# Project_Arduino_DUE_shield.net
KiCad netlist of a schematic drawn in Altium Designer
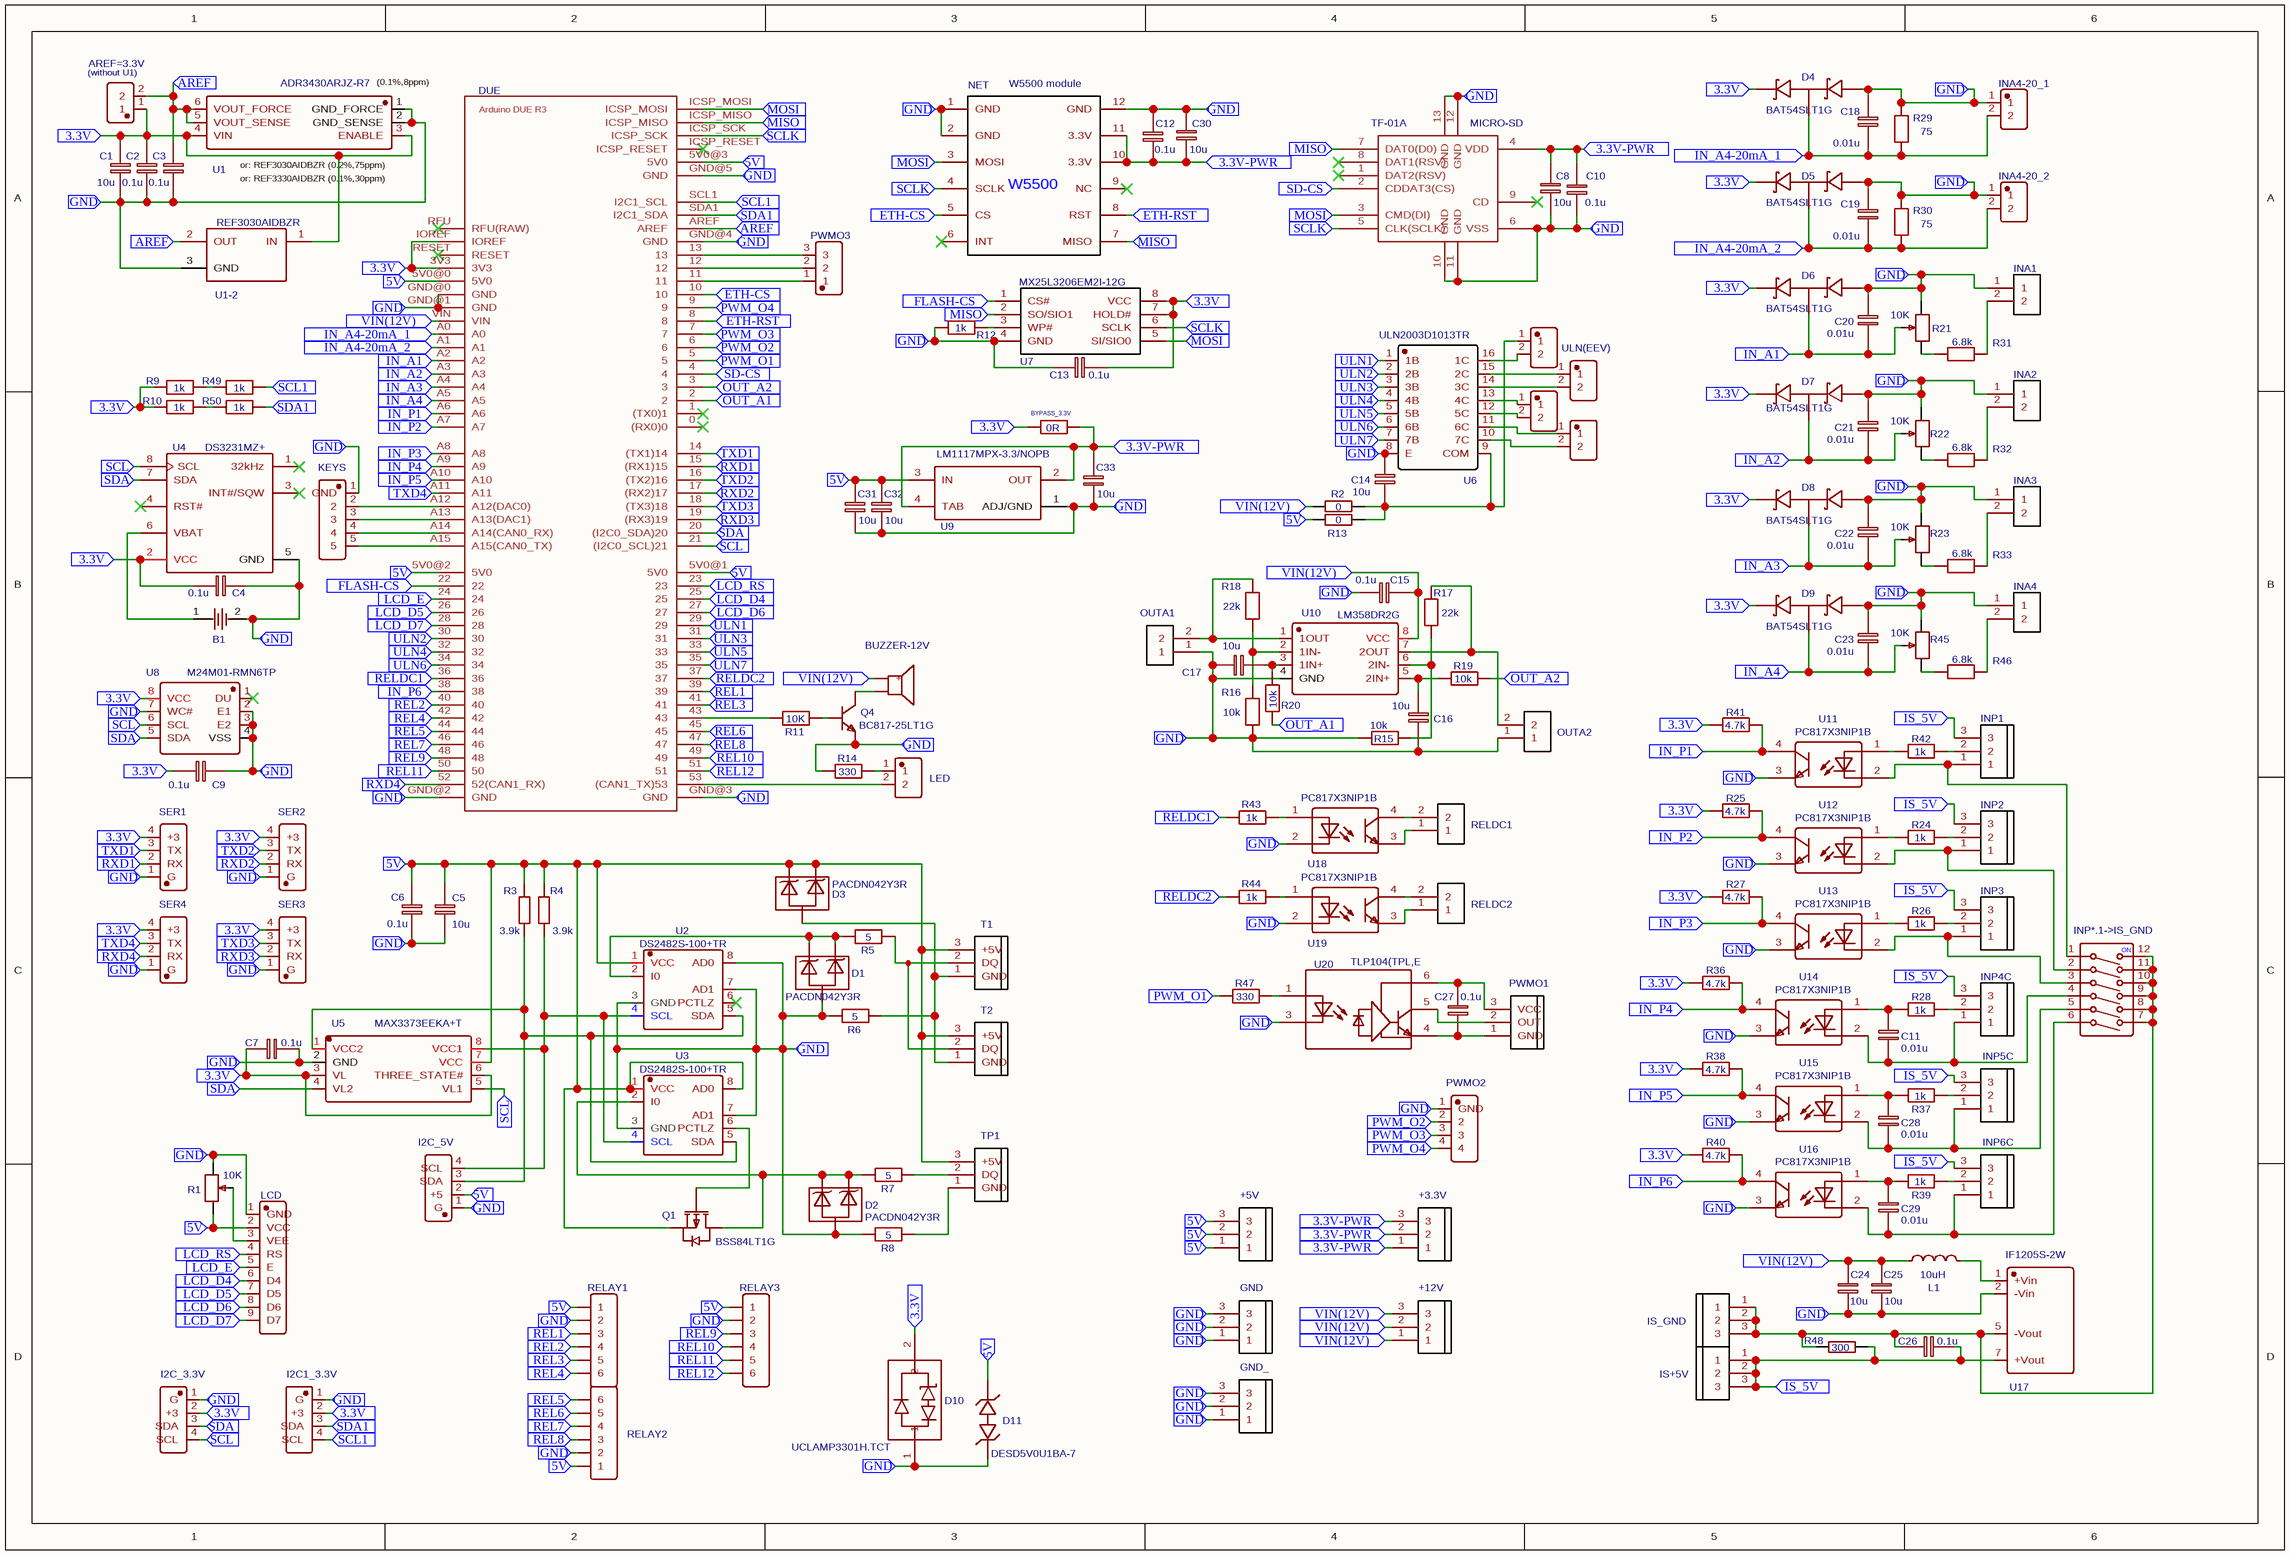
[diagram p0: Project_Arduino DUE shield.schdoc]

(export (version "E")
  (design (tool "Eeschema 10.0.6"))
  (components
    (comp (ref "+3.3V")
      (value "KF128L-5.08-3P")
      (fields (field (name "BOM_SUPPLIER PART") "C474941"))
      (libsource (lib "altium-import") (part "root_3_KF128L-5.08-3P_"))
    )
    (comp (ref "+5V")
      (value "KF128L-5.08-3P")
      (fields (field (name "BOM_SUPPLIER PART") "C474941"))
      (libsource (lib "altium-import") (part "root_3_KF128L-5.08-3P_"))
    )
    (comp (ref "+12V")
      (value "KF128L-5.08-3P")
      (fields (field (name "BOM_SUPPLIER PART") "C474941"))
      (libsource (lib "altium-import") (part "root_3_KF128L-5.08-3P_"))
    )
    (comp (ref "AREF=3.3V")
      (value "A2541WV-2P")
      (fields (field (name "BOM_SUPPLIER PART") "C225477") (field (name "CONTRIBUTOR") "LCSC"))
      (libsource (lib "altium-import") (part "root_2_A2541WV-2P_"))
    )
    (comp (ref "B1")
      (value "CR2032-BS-2-1")
      (fields (field (name "BOM_MANUFACTURER PART") "BS-2-1") (field (name "BOM_SUPPLIER PART") "C70376"))
      (libsource (lib "altium-import") (part "root_0_CR2032-BS-2-1_"))
    )
    (comp (ref "BUZZER-12V")
      (value "TMB12A12")
      (fields (field (name "BOM_SUPPLIER PART") "C96079"))
      (libsource (lib "altium-import") (part "root_0_TMB12A12_"))
    )
    (comp (ref "BYPASS_3.3V")
      (value "0R")
      (fields (field (name "CONTRIBUTOR") "LCEDA_Lib"))
      (libsource (lib "altium-import") (part "root_0_0R_"))
    )
    (comp (ref "C1")
      (value "10u")
      (fields
        (field (name "BOM_MANUFACTURER PART") "CL21A106KAYNNNE")
        (field (name "BOM_SUPPLIER PART") "C15850")
      )
      (libsource (lib "altium-import") (part "root_0_10u_"))
    )
    (comp (ref "C2")
      (value "0.1u")
      (fields
        (field (name "BOM_MANUFACTURER PART") "CC0603KRX7R9BB104")
        (field (name "BOM_SUPPLIER PART") "C14663")
      )
      (libsource (lib "") (part "root_0_0.1u__2"))
    )
    (comp (ref "C3")
      (value "0.1u")
      (fields
        (field (name "BOM_MANUFACTURER PART") "CC0603KRX7R9BB104")
        (field (name "BOM_SUPPLIER PART") "C14663")
      )
      (libsource (lib "") (part "root_0_0.1u__2"))
    )
    (comp (ref "C4")
      (value "0.1u")
      (fields
        (field (name "BOM_MANUFACTURER PART") "CC0603KRX7R9BB104")
        (field (name "BOM_SUPPLIER PART") "C14663")
      )
      (libsource (lib "") (part "root_3_0.1u__1"))
    )
    (comp (ref "C5")
      (value "10u")
      (fields
        (field (name "BOM_MANUFACTURER PART") "CL21A106KAYNNNE")
        (field (name "BOM_SUPPLIER PART") "C15850")
      )
      (libsource (lib "altium-import") (part "root_0_10u_"))
    )
    (comp (ref "C6")
      (value "0.1u")
      (fields
        (field (name "BOM_MANUFACTURER PART") "CC0603KRX7R9BB104")
        (field (name "BOM_SUPPLIER PART") "C14663")
      )
      (libsource (lib "") (part "root_0_0.1u__2"))
    )
    (comp (ref "C7")
      (value "0.1u")
      (fields
        (field (name "BOM_MANUFACTURER PART") "CC0603KRX7R9BB104")
        (field (name "BOM_SUPPLIER PART") "C14663")
      )
      (libsource (lib "") (part "root_1_0.1u__2"))
    )
    (comp (ref "C8")
      (value "10u")
      (fields
        (field (name "BOM_SUPPLIER PART") "C15850")
        (field (name "BOM_MANUFACTURER PART") "CL21A106KAYNNNE")
        (field (name "CONTRIBUTOR") "LCEDA_Lib")
      )
      (libsource (lib "altium-import") (part "root_3_10u_"))
    )
    (comp (ref "C9")
      (value "0.1u")
      (fields
        (field (name "BOM_MANUFACTURER PART") "CC0603KRX7R9BB104")
        (field (name "BOM_SUPPLIER PART") "C14663")
      )
      (libsource (lib "") (part "root_3_0.1u__1"))
    )
    (comp (ref "C10")
      (value "0.1u")
      (fields
        (field (name "BOM_SUPPLIER PART") "C14663")
        (field (name "BOM_MANUFACTURER PART") "CC0603KRX7R9BB104")
        (field (name "CONTRIBUTOR") "LCEDA_Lib")
      )
      (libsource (lib "") (part "root_1_0.1u__1"))
    )
    (comp (ref "C11")
      (value "0.01u")
      (fields
        (field (name "BOM_SUPPLIER PART") "C57112")
        (field (name "BOM_MANUFACTURER PART") "0603B103K500NT")
        (field (name "CONTRIBUTOR") "LCEDA_Lib")
      )
      (libsource (lib "altium-import") (part "root_3_0.01u_"))
    )
    (comp (ref "C12")
      (value "0.1u")
      (fields
        (field (name "BOM_SUPPLIER PART") "C14663")
        (field (name "BOM_MANUFACTURER PART") "CC0603KRX7R9BB104")
        (field (name "CONTRIBUTOR") "LCEDA_Lib")
      )
      (libsource (lib "") (part "root_1_0.1u__1"))
    )
    (comp (ref "C13")
      (value "0.1u")
      (fields
        (field (name "BOM_SUPPLIER PART") "C14663")
        (field (name "BOM_MANUFACTURER PART") "CC0603KRX7R9BB104")
        (field (name "CONTRIBUTOR") "LCEDA_Lib")
      )
      (libsource (lib "") (part "root_0_0.1u__1"))
    )
    (comp (ref "C14")
      (value "10u")
      (fields
        (field (name "BOM_MANUFACTURER PART") "CL21A106KAYNNNE")
        (field (name "BOM_SUPPLIER PART") "C15850")
      )
      (libsource (lib "") (part "root_0_10u__1"))
    )
    (comp (ref "C15")
      (value "0.1u")
      (fields
        (field (name "BOM_MANUFACTURER PART") "CC0603KRX7R9BB104")
        (field (name "BOM_SUPPLIER PART") "C14663")
      )
      (libsource (lib "altium-import") (part "root_3_0.1u_"))
    )
    (comp (ref "C16")
      (value "10u")
      (fields
        (field (name "BOM_MANUFACTURER PART") "CL21A106KAYNNNE")
        (field (name "BOM_SUPPLIER PART") "C15850")
      )
      (libsource (lib "altium-import") (part "root_0_10u_"))
    )
    (comp (ref "C17")
      (value "10u")
      (fields
        (field (name "BOM_MANUFACTURER PART") "CL21A106KAYNNNE")
        (field (name "BOM_SUPPLIER PART") "C15850")
      )
      (libsource (lib "altium-import") (part "root_1_10u_"))
    )
    (comp (ref "C18")
      (value "0.01u")
      (fields
        (field (name "BOM_MANUFACTURER PART") "0603B103K500NT")
        (field (name "BOM_SUPPLIER PART") "C57112")
      )
      (libsource (lib "altium-import") (part "root_0_0.01u_"))
    )
    (comp (ref "C19")
      (value "0.01u")
      (fields
        (field (name "BOM_MANUFACTURER PART") "0603B103K500NT")
        (field (name "BOM_SUPPLIER PART") "C57112")
      )
      (libsource (lib "altium-import") (part "root_0_0.01u_"))
    )
    (comp (ref "C20")
      (value "0.01u")
      (fields
        (field (name "BOM_MANUFACTURER PART") "0603B103K500NT")
        (field (name "BOM_SUPPLIER PART") "C57112")
      )
      (libsource (lib "altium-import") (part "root_0_0.01u_"))
    )
    (comp (ref "C21")
      (value "0.01u")
      (fields
        (field (name "BOM_MANUFACTURER PART") "0603B103K500NT")
        (field (name "BOM_SUPPLIER PART") "C57112")
      )
      (libsource (lib "altium-import") (part "root_0_0.01u_"))
    )
    (comp (ref "C22")
      (value "0.01u")
      (fields
        (field (name "BOM_MANUFACTURER PART") "0603B103K500NT")
        (field (name "BOM_SUPPLIER PART") "C57112")
      )
      (libsource (lib "altium-import") (part "root_0_0.01u_"))
    )
    (comp (ref "C23")
      (value "0.01u")
      (fields
        (field (name "BOM_MANUFACTURER PART") "0603B103K500NT")
        (field (name "BOM_SUPPLIER PART") "C57112")
      )
      (libsource (lib "altium-import") (part "root_0_0.01u_"))
    )
    (comp (ref "C24")
      (value "10u")
      (fields
        (field (name "BOM_SUPPLIER PART") "C15850")
        (field (name "BOM_MANUFACTURER PART") "CL21A106KAYNNNE")
        (field (name "CONTRIBUTOR") "LCEDA_Lib")
      )
      (libsource (lib "") (part "root_1_10u__1"))
    )
    (comp (ref "C25")
      (value "10u")
      (fields
        (field (name "BOM_SUPPLIER PART") "C15850")
        (field (name "BOM_MANUFACTURER PART") "CL21A106KAYNNNE")
        (field (name "CONTRIBUTOR") "LCEDA_Lib")
      )
      (libsource (lib "") (part "root_1_10u__1"))
    )
    (comp (ref "C26")
      (value "0.1u")
      (fields
        (field (name "BOM_MANUFACTURER PART") "CC0603KRX7R9BB104")
        (field (name "BOM_SUPPLIER PART") "C14663")
      )
      (libsource (lib "altium-import") (part "root_1_0.1u_"))
    )
    (comp (ref "C27")
      (value "0.1u")
      (fields
        (field (name "BOM_MANUFACTURER PART") "CC0603KRX7R9BB104")
        (field (name "BOM_SUPPLIER PART") "C14663")
      )
      (libsource (lib "altium-import") (part "root_0_0.1u_"))
    )
    (comp (ref "C28")
      (value "0.01u")
      (fields
        (field (name "BOM_SUPPLIER PART") "C57112")
        (field (name "BOM_MANUFACTURER PART") "0603B103K500NT")
        (field (name "CONTRIBUTOR") "LCEDA_Lib")
      )
      (libsource (lib "altium-import") (part "root_3_0.01u_"))
    )
    (comp (ref "C29")
      (value "0.01u")
      (fields
        (field (name "BOM_SUPPLIER PART") "C57112")
        (field (name "BOM_MANUFACTURER PART") "0603B103K500NT")
        (field (name "CONTRIBUTOR") "LCEDA_Lib")
      )
      (libsource (lib "altium-import") (part "root_3_0.01u_"))
    )
    (comp (ref "C30")
      (value "10u")
      (fields
        (field (name "BOM_SUPPLIER PART") "C15850")
        (field (name "BOM_MANUFACTURER PART") "CL21A106KAYNNNE")
        (field (name "CONTRIBUTOR") "LCEDA_Lib")
      )
      (libsource (lib "altium-import") (part "root_3_10u_"))
    )
    (comp (ref "C31")
      (value "10u")
      (fields
        (field (name "BOM_MANUFACTURER PART") "CL21A106KAYNNNE")
        (field (name "BOM_SUPPLIER PART") "C15850")
      )
      (libsource (lib "altium-import") (part "root_2_10u_"))
    )
    (comp (ref "C32")
      (value "10u")
      (fields
        (field (name "BOM_MANUFACTURER PART") "CL21A106KAYNNNE")
        (field (name "BOM_SUPPLIER PART") "C15850")
      )
      (libsource (lib "altium-import") (part "root_2_10u_"))
    )
    (comp (ref "C33")
      (value "10u")
      (fields
        (field (name "BOM_MANUFACTURER PART") "CL21A106KAYNNNE")
        (field (name "BOM_SUPPLIER PART") "C15850")
      )
      (libsource (lib "altium-import") (part "root_2_10u_"))
    )
    (comp (ref "D1")
      (value "PACDN042Y3R")
      (fields (field (name "BOM_SUPPLIER PART") "C233486") (field (name "CONTRIBUTOR") "LCSC"))
      (libsource (lib "altium-import") (part "root_2_PACDN042Y3R_"))
    )
    (comp (ref "D2")
      (value "PACDN042Y3R")
      (fields (field (name "BOM_SUPPLIER PART") "C233486") (field (name "CONTRIBUTOR") "LCSC"))
      (libsource (lib "altium-import") (part "root_2_PACDN042Y3R_"))
    )
    (comp (ref "D3")
      (value "PACDN042Y3R")
      (fields (field (name "BOM_SUPPLIER PART") "C233486") (field (name "CONTRIBUTOR") "LCSC"))
      (libsource (lib "altium-import") (part "root_2_PACDN042Y3R_"))
    )
    (comp (ref "D4")
      (value "BAT54SLT1G")
      (fields (field (name "BOM_SUPPLIER PART") "C19726"))
      (libsource (lib "altium-import") (part "root_0_BAT54SLT1G_"))
    )
    (comp (ref "D5")
      (value "BAT54SLT1G")
      (fields (field (name "BOM_SUPPLIER PART") "C19726"))
      (libsource (lib "altium-import") (part "root_0_BAT54SLT1G_"))
    )
    (comp (ref "D6")
      (value "BAT54SLT1G")
      (fields (field (name "BOM_SUPPLIER PART") "C19726"))
      (libsource (lib "altium-import") (part "root_0_BAT54SLT1G_"))
    )
    (comp (ref "D7")
      (value "BAT54SLT1G")
      (fields (field (name "BOM_SUPPLIER PART") "C19726"))
      (libsource (lib "altium-import") (part "root_0_BAT54SLT1G_"))
    )
    (comp (ref "D8")
      (value "BAT54SLT1G")
      (fields (field (name "BOM_SUPPLIER PART") "C19726"))
      (libsource (lib "altium-import") (part "root_0_BAT54SLT1G_"))
    )
    (comp (ref "D9")
      (value "BAT54SLT1G")
      (fields (field (name "BOM_SUPPLIER PART") "C19726"))
      (libsource (lib "altium-import") (part "root_0_BAT54SLT1G_"))
    )
    (comp (ref "D10")
      (value "UCLAMP3301H.TCT")
      (fields (field (name "BOM_SUPPLIER PART") "C117558") (field (name "CONTRIBUTOR") "LCSC"))
      (libsource (lib "altium-import") (part "root_1_UCLAMP3301H.TCT_"))
    )
    (comp (ref "D11")
      (value "DESD5V0U1BA-7")
      (fields (field (name "BOM_SUPPLIER PART") "C460442") (field (name "CONTRIBUTOR") "LCSC"))
      (libsource (lib "altium-import") (part "root_1_DESD5V0U1BA-7_"))
    )
    (comp (ref "DUE")
      (value "PA_DUE_BRD")
      (description "PatternAgents Due Shield Board Pattern")
      (fields (field (name "BOM_MANUFACTURER PART") "?") (field (name "CONTRIBUTOR") "PatternAgents"))
      (libsource (lib "altium-import") (part "root_0_PA_DUE_BRD_"))
    )
    (comp (ref "GND")
      (value "KF128L-5.08-3P")
      (fields (field (name "BOM_SUPPLIER PART") "C474941"))
      (libsource (lib "altium-import") (part "root_3_KF128L-5.08-3P_"))
    )
    (comp (ref "GND_")
      (value "KF128L-5.08-3P")
      (fields (field (name "BOM_SUPPLIER PART") "C474941"))
      (libsource (lib "altium-import") (part "root_3_KF128L-5.08-3P_"))
    )
    (comp (ref "I2C1_3.3V")
      (value "A2541WV-4P")
      (fields (field (name "BOM_SUPPLIER PART") "C225479") (field (name "CONTRIBUTOR") "LCSC"))
      (libsource (lib "") (part "root_1_A2541WV-4P__1"))
    )
    (comp (ref "I2C_3.3V")
      (value "A2541WV-4P")
      (fields (field (name "BOM_SUPPLIER PART") "C225479") (field (name "CONTRIBUTOR") "LCSC"))
      (libsource (lib "") (part "root_1_A2541WV-4P__1"))
    )
    (comp (ref "I2C_5V")
      (value "A2541WV-4P")
      (fields (field (name "BOM_SUPPLIER PART") "C225479") (field (name "CONTRIBUTOR") "LCSC"))
      (libsource (lib "") (part "root_1_A2541WV-4P__2"))
    )
    (comp (ref "INA1")
      (value "KF128L-5.08-2P")
      (fields (field (name "BOM_SUPPLIER PART") "C474940"))
      (libsource (lib "altium-import") (part "root_3_KF128L-5.08-2P_"))
    )
    (comp (ref "INA2")
      (value "KF128L-5.08-2P")
      (fields (field (name "BOM_SUPPLIER PART") "C474940"))
      (libsource (lib "altium-import") (part "root_3_KF128L-5.08-2P_"))
    )
    (comp (ref "INA3")
      (value "KF128L-5.08-2P")
      (fields (field (name "BOM_SUPPLIER PART") "C474940"))
      (libsource (lib "altium-import") (part "root_3_KF128L-5.08-2P_"))
    )
    (comp (ref "INA4")
      (value "KF128L-5.08-2P")
      (fields (field (name "BOM_SUPPLIER PART") "C474940"))
      (libsource (lib "altium-import") (part "root_3_KF128L-5.08-2P_"))
    )
    (comp (ref "INA4-20_1")
      (value "KF128L-3.5-2P")
      (fields (field (name "BOM_SUPPLIER PART") "C474930") (field (name "CONTRIBUTOR") "LCSC"))
      (libsource (lib "altium-import") (part "root_0_KF128L-3.5-2P_"))
    )
    (comp (ref "INA4-20_2")
      (value "KF128L-3.5-2P")
      (fields (field (name "BOM_SUPPLIER PART") "C474930") (field (name "CONTRIBUTOR") "LCSC"))
      (libsource (lib "altium-import") (part "root_0_KF128L-3.5-2P_"))
    )
    (comp (ref "INP*.1->IS_GND")
      (value "EM-06-Q")
      (fields (field (name "BOM_SUPPLIER PART") "C501580") (field (name "CONTRIBUTOR") "LCSC"))
      (libsource (lib "altium-import") (part "root_3_EM-06-Q_"))
    )
    (comp (ref "INP1")
      (value "KF128L-5.08-3P")
      (fields (field (name "BOM_SUPPLIER PART") "C474941"))
      (libsource (lib "altium-import") (part "root_3_KF128L-5.08-3P_"))
    )
    (comp (ref "INP2")
      (value "KF128L-5.08-3P")
      (fields (field (name "BOM_SUPPLIER PART") "C474941"))
      (libsource (lib "altium-import") (part "root_3_KF128L-5.08-3P_"))
    )
    (comp (ref "INP3")
      (value "KF128L-5.08-3P")
      (fields (field (name "BOM_SUPPLIER PART") "C474941"))
      (libsource (lib "altium-import") (part "root_3_KF128L-5.08-3P_"))
    )
    (comp (ref "INP4C")
      (value "KF128L-5.08-3P")
      (fields (field (name "BOM_SUPPLIER PART") "C474941"))
      (libsource (lib "altium-import") (part "root_3_KF128L-5.08-3P_"))
    )
    (comp (ref "INP5C")
      (value "KF128L-5.08-3P")
      (fields (field (name "BOM_SUPPLIER PART") "C474941"))
      (libsource (lib "altium-import") (part "root_3_KF128L-5.08-3P_"))
    )
    (comp (ref "INP6C")
      (value "KF128L-5.08-3P")
      (fields (field (name "BOM_SUPPLIER PART") "C474941"))
      (libsource (lib "altium-import") (part "root_3_KF128L-5.08-3P_"))
    )
    (comp (ref "IS+5V")
      (value "KF128L-5.08-3P")
      (fields (field (name "BOM_SUPPLIER PART") "C474941"))
      (libsource (lib "altium-import") (part "root_1_KF128L-5.08-3P_"))
    )
    (comp (ref "IS_GND")
      (value "KF128L-5.08-3P")
      (fields (field (name "BOM_SUPPLIER PART") "C474941"))
      (libsource (lib "altium-import") (part "root_1_KF128L-5.08-3P_"))
    )
    (comp (ref "KEYS")
      (value "A2541WV-5P")
      (fields (field (name "BOM_SUPPLIER PART") "C225480") (field (name "CONTRIBUTOR") "LCSC"))
      (libsource (lib "altium-import") (part "root_1_A2541WV-5P_"))
    )
    (comp (ref "L1")
      (value "10uH")
      (fields
        (field (name "BOM_MANUFACTURER PART") "FNR4018S100MT")
        (field (name "BOM_SUPPLIER PART") "C167808")
        (field (name "CONTRIBUTOR") "LCSC")
      )
      (libsource (lib "altium-import") (part "root_0_10uH_"))
    )
    (comp (ref "LCD")
      (value "PZ254V-11-09P")
      (fields (field (name "BOM_SUPPLIER PART") "C492408") (field (name "CONTRIBUTOR") "LCSC"))
      (libsource (lib "altium-import") (part "root_0_PZ254V-11-09P_"))
    )
    (comp (ref "LED")
      (value "A2541WV-2P")
      (fields (field (name "BOM_SUPPLIER PART") "C225477") (field (name "CONTRIBUTOR") "LCSC"))
      (libsource (lib "altium-import") (part "root_0_A2541WV-2P_"))
    )
    (comp (ref "MICRO-SD")
      (value "TF-01A")
      (fields (field (name "BOM_MANUFACTURER PART") "TF-15×15") (field (name "BOM_SUPPLIER PART") "C111196"))
      (libsource (lib "altium-import") (part "root_0_TF-01A_"))
    )
    (comp (ref "NET")
      (value "W5500 module")
      (fields (field (name "BOM_MANUFACTURER PART") "?") (field (name "CONTRIBUTOR") "RubenDijk"))
      (libsource (lib "altium-import") (part "root_0_W5500 module_"))
    )
    (comp (ref "OUTA1")
      (value "KF128L-5.08-2P")
      (fields
        (field (name "BOM_MANUFACTURER PART") "KF128L-3.5-2P")
        (field (name "BOM_SUPPLIER PART") "C474930")
      )
      (libsource (lib "altium-import") (part "root_1_KF128L-5.08-2P_"))
    )
    (comp (ref "OUTA2")
      (value "KF128L-5.08-2P")
      (fields
        (field (name "BOM_MANUFACTURER PART") "KF128L-3.5-2P")
        (field (name "BOM_SUPPLIER PART") "C474930")
      )
      (libsource (lib "") (part "root_3_KF128L-5.08-2P__1"))
    )
    (comp (ref "PWMO1")
      (value "KF128L-5.08-3P")
      (fields (field (name "BOM_SUPPLIER PART") "C474941"))
      (libsource (lib "altium-import") (part "root_3_KF128L-5.08-3P_"))
    )
    (comp (ref "PWMO2")
      (value "A2541WV-4P")
      (fields (field (name "BOM_SUPPLIER PART") "C225479") (field (name "CONTRIBUTOR") "LCSC"))
      (libsource (lib "altium-import") (part "root_1_A2541WV-4P_"))
    )
    (comp (ref "PWMO3")
      (value "A2541WV-3P")
      (fields (field (name "BOM_SUPPLIER PART") "C225478") (field (name "CONTRIBUTOR") "LCSC"))
      (libsource (lib "altium-import") (part "root_3_A2541WV-3P_"))
    )
    (comp (ref "Q1")
      (value "BSS84LT1G")
      (fields (field (name "BOM_MANUFACTURER PART") "LBSS84LT1G") (field (name "BOM_SUPPLIER PART") "C8492"))
      (libsource (lib "altium-import") (part "root_3_BSS84LT1G_"))
    )
    (comp (ref "Q4")
      (value "BC817-25LT1G")
      (fields (field (name "BOM_SUPPLIER PART") "C82635"))
      (libsource (lib "altium-import") (part "root_0_BC817-25LT1G_"))
    )
    (comp (ref "R1")
      (value "10K")
      (fields
        (field (name "BOM_MANUFACTURER PART") "3314J-1-103E")
        (field (name "BOM_SUPPLIER PART") "C36376")
      )
      (libsource (lib "altium-import") (part "root_0_10K_"))
    )
    (comp (ref "R2") (value "0") (libsource (lib "altium-import") (part "root_0_0_")))
    (comp (ref "R3")
      (value "3.9k")
      (fields
        (field (name "BOM_MANUFACTURER PART") "0603WAF3901T5E")
        (field (name "BOM_SUPPLIER PART") "C23018")
      )
      (libsource (lib "altium-import") (part "root_1_3.9k_"))
    )
    (comp (ref "R4")
      (value "3.9k")
      (fields
        (field (name "BOM_MANUFACTURER PART") "0603WAF3901T5E")
        (field (name "BOM_SUPPLIER PART") "C23018")
      )
      (libsource (lib "altium-import") (part "root_1_3.9k_"))
    )
    (comp (ref "R5")
      (value "5")
      (fields
        (field (name "BOM_SUPPLIER PART") "C25197")
        (field (name "BOM_MANUFACTURER PART") "0603WAF510KT5E")
        (field (name "CONTRIBUTOR") "LCEDA_Lib")
      )
      (libsource (lib "altium-import") (part "root_0_5_"))
    )
    (comp (ref "R6")
      (value "5")
      (fields
        (field (name "BOM_SUPPLIER PART") "C25197")
        (field (name "BOM_MANUFACTURER PART") "0603WAF510KT5E")
        (field (name "CONTRIBUTOR") "LCEDA_Lib")
      )
      (libsource (lib "altium-import") (part "root_0_5_"))
    )
    (comp (ref "R7")
      (value "5")
      (fields
        (field (name "BOM_SUPPLIER PART") "C25197")
        (field (name "BOM_MANUFACTURER PART") "0603WAF510KT5E")
        (field (name "CONTRIBUTOR") "LCEDA_Lib")
      )
      (libsource (lib "altium-import") (part "root_0_5_"))
    )
    (comp (ref "R8")
      (value "5")
      (fields
        (field (name "BOM_SUPPLIER PART") "C25197")
        (field (name "BOM_MANUFACTURER PART") "0603WAF510KT5E")
        (field (name "CONTRIBUTOR") "LCEDA_Lib")
      )
      (libsource (lib "altium-import") (part "root_0_5_"))
    )
    (comp (ref "R9")
      (value "1k")
      (fields
        (field (name "BOM_SUPPLIER PART") "C21190")
        (field (name "BOM_MANUFACTURER PART") "0603WAF1001T5E")
        (field (name "CONTRIBUTOR") "LCEDA_Lib")
      )
      (libsource (lib "altium-import") (part "root_0_1k_"))
    )
    (comp (ref "R10")
      (value "1k")
      (fields
        (field (name "BOM_SUPPLIER PART") "C21190")
        (field (name "BOM_MANUFACTURER PART") "0603WAF1001T5E")
        (field (name "CONTRIBUTOR") "LCEDA_Lib")
      )
      (libsource (lib "altium-import") (part "root_0_1k_"))
    )
    (comp (ref "R11")
      (value "10K")
      (fields
        (field (name "BOM_MANUFACTURER PART") "0603WAF1002T5E")
        (field (name "BOM_SUPPLIER PART") "C25804")
      )
      (libsource (lib "altium-import") (part "root_2_10K_"))
    )
    (comp (ref "R12")
      (value "1k")
      (fields
        (field (name "BOM_SUPPLIER PART") "C21190")
        (field (name "BOM_MANUFACTURER PART") "0603WAF1001T5E")
        (field (name "CONTRIBUTOR") "LCEDA_Lib")
      )
      (libsource (lib "altium-import") (part "root_0_1k_"))
    )
    (comp (ref "R13") (value "0") (libsource (lib "altium-import") (part "root_0_0_")))
    (comp (ref "R14")
      (value "330")
      (fields
        (field (name "BOM_SUPPLIER PART") "C23138")
        (field (name "BOM_MANUFACTURER PART") "0603WAF3300T5E")
        (field (name "CONTRIBUTOR") "LCEDA_Lib")
      )
      (libsource (lib "altium-import") (part "root_2_330_"))
    )
    (comp (ref "R15")
      (value "10k")
      (fields
        (field (name "BOM_MANUFACTURER PART") "0603WAF1002T5E")
        (field (name "BOM_SUPPLIER PART") "C25804")
      )
      (libsource (lib "altium-import") (part "root_0_10k_"))
    )
    (comp (ref "R16")
      (value "10k")
      (fields
        (field (name "BOM_MANUFACTURER PART") "0603WAF1002T5E")
        (field (name "BOM_SUPPLIER PART") "C25804")
      )
      (libsource (lib "altium-import") (part "root_1_10k_"))
    )
    (comp (ref "R17")
      (value "22k")
      (fields
        (field (name "BOM_MANUFACTURER PART") "0603WAF2202T5E")
        (field (name "BOM_SUPPLIER PART") "C31850")
      )
      (libsource (lib "altium-import") (part "root_1_22k_"))
    )
    (comp (ref "R18")
      (value "22k")
      (fields
        (field (name "BOM_MANUFACTURER PART") "0603WAF2202T5E")
        (field (name "BOM_SUPPLIER PART") "C31850")
      )
      (libsource (lib "altium-import") (part "root_1_22k_"))
    )
    (comp (ref "R19")
      (value "10k")
      (fields
        (field (name "BOM_MANUFACTURER PART") "0603WAF1002T5E")
        (field (name "BOM_SUPPLIER PART") "C25804")
      )
      (libsource (lib "altium-import") (part "root_0_10k_"))
    )
    (comp (ref "R20")
      (value "10k")
      (fields
        (field (name "BOM_MANUFACTURER PART") "0603WAF1002T5E")
        (field (name "BOM_SUPPLIER PART") "C25804")
      )
      (libsource (lib "altium-import") (part "root_1_10k_"))
    )
    (comp (ref "R21")
      (value "10K")
      (fields
        (field (name "BOM_MANUFACTURER PART") "3314J-1-103E")
        (field (name "BOM_SUPPLIER PART") "C36376")
      )
      (libsource (lib "") (part "root_0_10K__1"))
    )
    (comp (ref "R22")
      (value "10K")
      (fields
        (field (name "BOM_MANUFACTURER PART") "3314J-1-103E")
        (field (name "BOM_SUPPLIER PART") "C36376")
      )
      (libsource (lib "") (part "root_0_10K__1"))
    )
    (comp (ref "R23")
      (value "10K")
      (fields
        (field (name "BOM_MANUFACTURER PART") "3314J-1-103E")
        (field (name "BOM_SUPPLIER PART") "C36376")
      )
      (libsource (lib "") (part "root_0_10K__1"))
    )
    (comp (ref "R24")
      (value "1k")
      (fields
        (field (name "BOM_MANUFACTURER PART") "0603WAF1001T5E")
        (field (name "BOM_SUPPLIER PART") "C21190")
      )
      (libsource (lib "") (part "root_0_1k__1"))
    )
    (comp (ref "R25")
      (value "4.7k")
      (fields
        (field (name "BOM_MANUFACTURER PART") "0603WAF4701T5E")
        (field (name "BOM_SUPPLIER PART") "C23162")
      )
      (libsource (lib "altium-import") (part "root_0_4.7k_"))
    )
    (comp (ref "R26")
      (value "1k")
      (fields
        (field (name "BOM_MANUFACTURER PART") "0603WAF1001T5E")
        (field (name "BOM_SUPPLIER PART") "C21190")
      )
      (libsource (lib "") (part "root_0_1k__1"))
    )
    (comp (ref "R27")
      (value "4.7k")
      (fields
        (field (name "BOM_MANUFACTURER PART") "0603WAF4701T5E")
        (field (name "BOM_SUPPLIER PART") "C23162")
      )
      (libsource (lib "altium-import") (part "root_0_4.7k_"))
    )
    (comp (ref "R28")
      (value "1k")
      (fields
        (field (name "BOM_MANUFACTURER PART") "0603WAF1001T5E")
        (field (name "BOM_SUPPLIER PART") "C21190")
      )
      (libsource (lib "") (part "root_0_1k__1"))
    )
    (comp (ref "R29")
      (value "75")
      (fields
        (field (name "BOM_MANUFACTURER PART") "0805W8F750JT5E")
        (field (name "BOM_SUPPLIER PART") "C20638")
      )
      (libsource (lib "altium-import") (part "root_3_75_"))
    )
    (comp (ref "R30")
      (value "75")
      (fields
        (field (name "BOM_MANUFACTURER PART") "0805W8F750JT5E")
        (field (name "BOM_SUPPLIER PART") "C20638")
      )
      (libsource (lib "altium-import") (part "root_3_75_"))
    )
    (comp (ref "R31")
      (value "6.8k")
      (fields
        (field (name "BOM_MANUFACTURER PART") "0603WAF6801T5E")
        (field (name "BOM_SUPPLIER PART") "C23212")
      )
      (libsource (lib "altium-import") (part "root_0_6.8k_"))
    )
    (comp (ref "R32")
      (value "6.8k")
      (fields
        (field (name "BOM_MANUFACTURER PART") "0603WAF6801T5E")
        (field (name "BOM_SUPPLIER PART") "C23212")
      )
      (libsource (lib "altium-import") (part "root_0_6.8k_"))
    )
    (comp (ref "R33")
      (value "6.8k")
      (fields
        (field (name "BOM_MANUFACTURER PART") "0603WAF6801T5E")
        (field (name "BOM_SUPPLIER PART") "C23212")
      )
      (libsource (lib "altium-import") (part "root_0_6.8k_"))
    )
    (comp (ref "R36")
      (value "4.7k")
      (fields
        (field (name "BOM_MANUFACTURER PART") "0603WAF4701T5E")
        (field (name "BOM_SUPPLIER PART") "C23162")
      )
      (libsource (lib "altium-import") (part "root_0_4.7k_"))
    )
    (comp (ref "R37")
      (value "1k")
      (fields
        (field (name "BOM_MANUFACTURER PART") "0603WAF1001T5E")
        (field (name "BOM_SUPPLIER PART") "C21190")
      )
      (libsource (lib "") (part "root_0_1k__1"))
    )
    (comp (ref "R38")
      (value "4.7k")
      (fields
        (field (name "BOM_MANUFACTURER PART") "0603WAF4701T5E")
        (field (name "BOM_SUPPLIER PART") "C23162")
      )
      (libsource (lib "altium-import") (part "root_0_4.7k_"))
    )
    (comp (ref "R39")
      (value "1k")
      (fields
        (field (name "BOM_MANUFACTURER PART") "0603WAF1001T5E")
        (field (name "BOM_SUPPLIER PART") "C21190")
      )
      (libsource (lib "") (part "root_0_1k__1"))
    )
    (comp (ref "R40")
      (value "4.7k")
      (fields
        (field (name "BOM_MANUFACTURER PART") "0603WAF4701T5E")
        (field (name "BOM_SUPPLIER PART") "C23162")
      )
      (libsource (lib "altium-import") (part "root_0_4.7k_"))
    )
    (comp (ref "R41")
      (value "4.7k")
      (fields
        (field (name "BOM_MANUFACTURER PART") "0603WAF4701T5E")
        (field (name "BOM_SUPPLIER PART") "C23162")
      )
      (libsource (lib "altium-import") (part "root_0_4.7k_"))
    )
    (comp (ref "R42")
      (value "1k")
      (fields
        (field (name "BOM_MANUFACTURER PART") "0603WAF1001T5E")
        (field (name "BOM_SUPPLIER PART") "C21190")
      )
      (libsource (lib "") (part "root_0_1k__1"))
    )
    (comp (ref "R43")
      (value "1k")
      (fields
        (field (name "BOM_SUPPLIER PART") "C21190")
        (field (name "BOM_MANUFACTURER PART") "0603WAF1001T5E")
        (field (name "CONTRIBUTOR") "LCEDA_Lib")
      )
      (libsource (lib "altium-import") (part "root_0_1k_"))
    )
    (comp (ref "R44")
      (value "1k")
      (fields
        (field (name "BOM_SUPPLIER PART") "C21190")
        (field (name "BOM_MANUFACTURER PART") "0603WAF1001T5E")
        (field (name "CONTRIBUTOR") "LCEDA_Lib")
      )
      (libsource (lib "altium-import") (part "root_0_1k_"))
    )
    (comp (ref "R45")
      (value "10K")
      (fields
        (field (name "BOM_MANUFACTURER PART") "3314J-1-103E")
        (field (name "BOM_SUPPLIER PART") "C36376")
      )
      (libsource (lib "") (part "root_0_10K__1"))
    )
    (comp (ref "R46")
      (value "6.8k")
      (fields
        (field (name "BOM_MANUFACTURER PART") "0603WAF6801T5E")
        (field (name "BOM_SUPPLIER PART") "C23212")
      )
      (libsource (lib "altium-import") (part "root_0_6.8k_"))
    )
    (comp (ref "R47")
      (value "330")
      (fields
        (field (name "BOM_SUPPLIER PART") "C23138")
        (field (name "BOM_MANUFACTURER PART") "0603WAF3300T5E")
        (field (name "CONTRIBUTOR") "LCEDA_Lib")
      )
      (libsource (lib "altium-import") (part "root_0_330_"))
    )
    (comp (ref "R48")
      (value "300")
      (fields
        (field (name "BOM_MANUFACTURER PART") "1206W4F3000T5E")
        (field (name "BOM_SUPPLIER PART") "C17887")
      )
      (libsource (lib "altium-import") (part "root_0_300_"))
    )
    (comp (ref "R49")
      (value "1k")
      (fields
        (field (name "BOM_SUPPLIER PART") "C21190")
        (field (name "BOM_MANUFACTURER PART") "0603WAF1001T5E")
        (field (name "CONTRIBUTOR") "LCEDA_Lib")
      )
      (libsource (lib "altium-import") (part "root_0_1k_"))
    )
    (comp (ref "R50")
      (value "1k")
      (fields
        (field (name "BOM_SUPPLIER PART") "C21190")
        (field (name "BOM_MANUFACTURER PART") "0603WAF1001T5E")
        (field (name "CONTRIBUTOR") "LCEDA_Lib")
      )
      (libsource (lib "altium-import") (part "root_0_1k_"))
    )
    (comp (ref "RELAY1")
      (value "Header-Male-2.54_1x6")
      (fields (field (name "BOM_SUPPLIER PART") "C37208"))
      (libsource (lib "") (part "root_0_Header-Male-2.54_1x6__1"))
    )
    (comp (ref "RELAY2")
      (value "Header-Male-2.54_1x6")
      (fields (field (name "BOM_SUPPLIER PART") "C37208"))
      (libsource (lib "altium-import") (part "root_0_Header-Male-2.54_1x6_"))
    )
    (comp (ref "RELAY3")
      (value "Header-Male-2.54_1x6")
      (fields (field (name "BOM_SUPPLIER PART") "C37208"))
      (libsource (lib "") (part "root_0_Header-Male-2.54_1x6__1"))
    )
    (comp (ref "RELDC1")
      (value "KF128L-5.08-2P")
      (fields (field (name "BOM_SUPPLIER PART") "C474940"))
      (libsource (lib "") (part "root_3_KF128L-5.08-2P__1"))
    )
    (comp (ref "RELDC2")
      (value "KF128L-5.08-2P")
      (fields (field (name "BOM_SUPPLIER PART") "C474940"))
      (libsource (lib "") (part "root_3_KF128L-5.08-2P__1"))
    )
    (comp (ref "SER1")
      (value "A2541WV-4P")
      (fields (field (name "BOM_SUPPLIER PART") "C225479") (field (name "CONTRIBUTOR") "LCSC"))
      (libsource (lib "altium-import") (part "root_3_A2541WV-4P_"))
    )
    (comp (ref "SER2")
      (value "A2541WV-4P")
      (fields (field (name "BOM_SUPPLIER PART") "C225479") (field (name "CONTRIBUTOR") "LCSC"))
      (libsource (lib "altium-import") (part "root_3_A2541WV-4P_"))
    )
    (comp (ref "SER3")
      (value "A2541WV-4P")
      (fields (field (name "BOM_SUPPLIER PART") "C225479") (field (name "CONTRIBUTOR") "LCSC"))
      (libsource (lib "altium-import") (part "root_3_A2541WV-4P_"))
    )
    (comp (ref "SER4")
      (value "A2541WV-4P")
      (fields (field (name "BOM_SUPPLIER PART") "C225479") (field (name "CONTRIBUTOR") "LCSC"))
      (libsource (lib "altium-import") (part "root_3_A2541WV-4P_"))
    )
    (comp (ref "T1")
      (value "KF128L-5.08-3P")
      (fields (field (name "BOM_SUPPLIER PART") "C474941"))
      (libsource (lib "altium-import") (part "root_3_KF128L-5.08-3P_"))
    )
    (comp (ref "T2")
      (value "KF128L-5.08-3P")
      (fields (field (name "BOM_SUPPLIER PART") "C474941"))
      (libsource (lib "altium-import") (part "root_3_KF128L-5.08-3P_"))
    )
    (comp (ref "TP1")
      (value "KF128L-5.08-3P")
      (fields (field (name "BOM_SUPPLIER PART") "C474941"))
      (libsource (lib "altium-import") (part "root_3_KF128L-5.08-3P_"))
    )
    (comp (ref "U1")
      (value "ADR3430ARJZ-R7")
      (fields (field (name "BOM_SUPPLIER PART") "C138535") (field (name "CONTRIBUTOR") "LCSC"))
      (libsource (lib "altium-import") (part "root_0_ADR3430ARJZ-R7_"))
    )
    (comp (ref "U1-2")
      (value "REF3030AIDBZR")
      (fields (field (name "BOM_SUPPLIER PART") "C38423"))
      (libsource (lib "altium-import") (part "root_0_REF3030AIDBZR_"))
    )
    (comp (ref "U2")
      (value "DS2482S-100+TR")
      (fields
        (field (name "BOM_MANUFACTURER PART") "DS2482S-100+T&R")
        (field (name "BOM_SUPPLIER PART") "C143306")
        (field (name "CONTRIBUTOR") "LCSC")
      )
      (libsource (lib "altium-import") (part "root_0_DS2482S-100+TR_"))
    )
    (comp (ref "U3")
      (value "DS2482S-100+TR")
      (fields
        (field (name "BOM_MANUFACTURER PART") "DS2482S-100+T&R")
        (field (name "BOM_SUPPLIER PART") "C143306")
        (field (name "CONTRIBUTOR") "LCSC")
      )
      (libsource (lib "altium-import") (part "root_0_DS2482S-100+TR_"))
    )
    (comp (ref "U4")
      (value "DS3231MZ+")
      (fields (field (name "BOM_SUPPLIER PART") "C107410"))
      (libsource (lib "altium-import") (part "root_0_DS3231MZ+_"))
    )
    (comp (ref "U5")
      (value "MAX3373EEKA+T")
      (fields (field (name "BOM_SUPPLIER PART") "C116658") (field (name "CONTRIBUTOR") "LCSC"))
      (libsource (lib "altium-import") (part "root_0_MAX3373EEKA+T_"))
    )
    (comp (ref "U6")
      (value "ULN2003D1013TR")
      (fields (field (name "BOM_MANUFACTURER PART") "ULN2003ADR") (field (name "BOM_SUPPLIER PART") "C7512"))
      (libsource (lib "altium-import") (part "root_0_ULN2003D1013TR_"))
    )
    (comp (ref "U7")
      (value "MX25L3206EM2I-12G")
      (fields (field (name "BOM_SUPPLIER PART") "C16142"))
      (libsource (lib "altium-import") (part "root_0_MX25L3206EM2I-12G_"))
    )
    (comp (ref "U8")
      (value "M24M01-RMN6TP")
      (fields (field (name "BOM_SUPPLIER PART") "C79990"))
      (libsource (lib "altium-import") (part "root_0_M24M01-RMN6TP_"))
    )
    (comp (ref "U9")
      (value "LM1117MPX-3.3/NOPB")
      (fields
        (field (name "BOM_MANUFACTURER PART") "LM1117IMPX-3.3/NOPB")
        (field (name "BOM_SUPPLIER PART") "C23984")
      )
      (libsource (lib "altium-import") (part "root_0_LM1117MPX-3.3/NOPB_"))
    )
    (comp (ref "U10")
      (value "LM358DR2G")
      (fields (field (name "BOM_SUPPLIER PART") "C7950"))
      (libsource (lib "altium-import") (part "root_0_LM358DR2G_"))
    )
    (comp (ref "U11")
      (value "PC817X3NIP1B")
      (fields
        (field (name "BOM_MANUFACTURER PART") "EL357N(C)(TA)-G")
        (field (name "BOM_SUPPLIER PART") "C29981")
        (field (name "CONTRIBUTOR") "LCSC")
      )
      (libsource (lib "altium-import") (part "root_0_PC817X3NIP1B_"))
    )
    (comp (ref "U12")
      (value "PC817X3NIP1B")
      (fields
        (field (name "BOM_MANUFACTURER PART") "EL357N(C)(TA)-G")
        (field (name "BOM_SUPPLIER PART") "C29981")
        (field (name "CONTRIBUTOR") "LCSC")
      )
      (libsource (lib "altium-import") (part "root_0_PC817X3NIP1B_"))
    )
    (comp (ref "U13")
      (value "PC817X3NIP1B")
      (fields
        (field (name "BOM_MANUFACTURER PART") "EL357N(C)(TA)-G")
        (field (name "BOM_SUPPLIER PART") "C29981")
        (field (name "CONTRIBUTOR") "LCSC")
      )
      (libsource (lib "altium-import") (part "root_0_PC817X3NIP1B_"))
    )
    (comp (ref "U14")
      (value "PC817X3NIP1B")
      (fields
        (field (name "BOM_MANUFACTURER PART") "EL357N(C)(TA)-G")
        (field (name "BOM_SUPPLIER PART") "C29981")
        (field (name "CONTRIBUTOR") "LCSC")
      )
      (libsource (lib "altium-import") (part "root_0_PC817X3NIP1B_"))
    )
    (comp (ref "U15")
      (value "PC817X3NIP1B")
      (fields
        (field (name "BOM_MANUFACTURER PART") "EL357N(C)(TA)-G")
        (field (name "BOM_SUPPLIER PART") "C29981")
        (field (name "CONTRIBUTOR") "LCSC")
      )
      (libsource (lib "altium-import") (part "root_0_PC817X3NIP1B_"))
    )
    (comp (ref "U16")
      (value "PC817X3NIP1B")
      (fields
        (field (name "BOM_MANUFACTURER PART") "EL357N(C)(TA)-G")
        (field (name "BOM_SUPPLIER PART") "C29981")
        (field (name "CONTRIBUTOR") "LCSC")
      )
      (libsource (lib "altium-import") (part "root_0_PC817X3NIP1B_"))
    )
    (comp (ref "U17")
      (value "IF1205S-2W")
      (fields (field (name "BOM_SUPPLIER PART") "C494963") (field (name "CONTRIBUTOR") "LCSC"))
      (libsource (lib "altium-import") (part "root_0_IF1205S-2W_"))
    )
    (comp (ref "U18")
      (value "PC817X3NIP1B")
      (fields
        (field (name "BOM_MANUFACTURER PART") "EL357N(C)(TA)-G")
        (field (name "BOM_SUPPLIER PART") "C29981")
        (field (name "CONTRIBUTOR") "LCSC")
      )
      (libsource (lib "") (part "root_0_PC817X3NIP1B__1"))
    )
    (comp (ref "U19")
      (value "PC817X3NIP1B")
      (fields
        (field (name "BOM_MANUFACTURER PART") "EL357N(C)(TA)-G")
        (field (name "BOM_SUPPLIER PART") "C29981")
        (field (name "CONTRIBUTOR") "LCSC")
      )
      (libsource (lib "") (part "root_0_PC817X3NIP1B__1"))
    )
    (comp (ref "U20")
      (value "TLP104(TPL,E")
      (fields (field (name "BOM_SUPPLIER PART") "C48236") (field (name "CONTRIBUTOR") "LCSC"))
      (libsource (lib "altium-import") (part "root_0_TLP104(TPL,E_"))
    )
    (comp (ref "ULN(EEV)")
      (value "KF128L-3.5-2P")
      (fields (field (name "BOM_SUPPLIER PART") "C474930") (field (name "CONTRIBUTOR") "LCSC"))
      (libsource (lib "altium-import") (part "root_0_KF128L-3.5-2P_"))
    )
    (comp (ref "ULN(EEV)1")
      (value "KF128L-3.5-2P")
      (fields (field (name "BOM_SUPPLIER PART") "C474930") (field (name "CONTRIBUTOR") "LCSC"))
      (libsource (lib "altium-import") (part "root_0_KF128L-3.5-2P_"))
    )
    (comp (ref "ULN(EEV)2")
      (value "KF128L-3.5-2P")
      (fields (field (name "BOM_SUPPLIER PART") "C474930") (field (name "CONTRIBUTOR") "LCSC"))
      (libsource (lib "altium-import") (part "root_0_KF128L-3.5-2P_"))
    )
    (comp (ref "ULN(EEV)3")
      (value "KF128L-3.5-2P")
      (fields (field (name "BOM_SUPPLIER PART") "C474930") (field (name "CONTRIBUTOR") "LCSC"))
      (libsource (lib "altium-import") (part "root_0_KF128L-3.5-2P_"))
    )
  )
  (nets
    (net (code "1") (name "/3.3V") (class "Default")
      (node (ref "AREF=3.3V") (pin "1") (pinfunction "1_1") (pintype "passive"))
      (node (ref "BYPASS_3.3V") (pin "1") (pinfunction "1_1") (pintype "passive"))
      (node (ref "C1") (pin "1") (pinfunction "1_1") (pintype "passive"))
      (node (ref "C13") (pin "2") (pinfunction "2_2") (pintype "passive"))
      (node (ref "C2") (pin "1") (pinfunction "1_1") (pintype "passive"))
      (node (ref "C4") (pin "2") (pinfunction "2_2") (pintype "passive"))
      (node (ref "C7") (pin "1") (pinfunction "1_1") (pintype "passive"))
      (node (ref "C9") (pin "2") (pinfunction "2_2") (pintype "passive"))
      (node (ref "D10") (pin "2") (pinfunction "2_2") (pintype "passive"))
      (node (ref "D4") (pin "2") (pinfunction "C_2") (pintype "passive"))
      (node (ref "D5") (pin "2") (pinfunction "C_2") (pintype "passive"))
      (node (ref "D6") (pin "2") (pinfunction "C_2") (pintype "passive"))
      (node (ref "D7") (pin "2") (pinfunction "C_2") (pintype "passive"))
      (node (ref "D8") (pin "2") (pinfunction "C_2") (pintype "passive"))
      (node (ref "D9") (pin "2") (pinfunction "C_2") (pintype "passive"))
      (node (ref "DUE") (pin "3V3") (pinfunction "3V3_3V3") (pintype "passive"))
      (node (ref "DUE") (pin "IOREF") (pinfunction "IOREF_IOREF") (pintype "passive"))
      (node (ref "I2C1_3.3V") (pin "2") (pinfunction "+3_2") (pintype "passive"))
      (node (ref "I2C_3.3V") (pin "2") (pinfunction "+3_2") (pintype "passive"))
      (node (ref "R10") (pin "1") (pinfunction "1_1") (pintype "passive"))
      (node (ref "R25") (pin "2") (pinfunction "2_2") (pintype "passive"))
      (node (ref "R27") (pin "2") (pinfunction "2_2") (pintype "passive"))
      (node (ref "R36") (pin "2") (pinfunction "2_2") (pintype "passive"))
      (node (ref "R38") (pin "2") (pinfunction "2_2") (pintype "passive"))
      (node (ref "R40") (pin "2") (pinfunction "2_2") (pintype "passive"))
      (node (ref "R41") (pin "2") (pinfunction "2_2") (pintype "passive"))
      (node (ref "R9") (pin "1") (pinfunction "1_1") (pintype "passive"))
      (node (ref "SER1") (pin "4") (pinfunction "+3_4") (pintype "passive"))
      (node (ref "SER2") (pin "4") (pinfunction "+3_4") (pintype "passive"))
      (node (ref "SER3") (pin "4") (pinfunction "+3_4") (pintype "passive"))
      (node (ref "SER4") (pin "4") (pinfunction "+3_4") (pintype "passive"))
      (node (ref "U1") (pin "3") (pinfunction "ENABLE_3") (pintype "passive"))
      (node (ref "U1") (pin "4") (pinfunction "VIN_4") (pintype "passive"))
      (node (ref "U1-2") (pin "1") (pinfunction "IN_1") (pintype "passive"))
      (node (ref "U4") (pin "2") (pinfunction "VCC_2") (pintype "passive"))
      (node (ref "U5") (pin "3") (pinfunction "VL_3") (pintype "passive"))
      (node (ref "U5") (pin "6") (pinfunction "THREE_STATE#_6") (pintype "passive"))
      (node (ref "U7") (pin "7") (pinfunction "HOLD#_7") (pintype "passive"))
      (node (ref "U7") (pin "8") (pinfunction "VCC_8") (pintype "passive"))
      (node (ref "U8") (pin "8") (pinfunction "VCC_8") (pintype "passive"))
    )
    (net (code "2") (name "/3.3V-PWR") (class "Default")
      (node (ref "+3.3V") (pin "1") (pinfunction "GND_1") (pintype "passive"))
      (node (ref "+3.3V") (pin "2") (pinfunction "DQ_2") (pintype "passive"))
      (node (ref "+3.3V") (pin "3") (pinfunction "+5V_3") (pintype "passive"))
      (node (ref "BYPASS_3.3V") (pin "2") (pinfunction "2_2") (pintype "passive"))
      (node (ref "C10") (pin "2") (pinfunction "2_2") (pintype "passive"))
      (node (ref "C12") (pin "1") (pinfunction "1_1") (pintype "passive"))
      (node (ref "C30") (pin "2") (pinfunction "2_2") (pintype "passive"))
      (node (ref "C33") (pin "2") (pinfunction "2_2") (pintype "passive"))
      (node (ref "C8") (pin "1") (pinfunction "1_1") (pintype "passive"))
      (node (ref "MICRO-SD") (pin "4") (pinfunction "VDD_4") (pintype "passive"))
      (node (ref "NET") (pin "10") (pinfunction "3.3V_10") (pintype "passive"))
      (node (ref "NET") (pin "11") (pinfunction "3.3V_11") (pintype "passive"))
      (node (ref "U9") (pin "2") (pinfunction "OUT_2") (pintype "passive"))
      (node (ref "U9") (pin "4") (pinfunction "TAB_4") (pintype "passive"))
    )
    (net (code "3") (name "/5V") (class "Default")
      (node (ref "+5V") (pin "1") (pinfunction "GND_1") (pintype "passive"))
      (node (ref "+5V") (pin "2") (pinfunction "DQ_2") (pintype "passive"))
      (node (ref "+5V") (pin "3") (pinfunction "+5V_3") (pintype "passive"))
      (node (ref "C31") (pin "2") (pinfunction "2_2") (pintype "passive"))
      (node (ref "C32") (pin "2") (pinfunction "2_2") (pintype "passive"))
      (node (ref "C5") (pin "1") (pinfunction "1_1") (pintype "passive"))
      (node (ref "C6") (pin "1") (pinfunction "1_1") (pintype "passive"))
      (node (ref "D11") (pin "2") (pinfunction "2_2") (pintype "passive"))
      (node (ref "D3") (pin "1") (pinfunction "1_1") (pintype "passive"))
      (node (ref "D3") (pin "2") (pinfunction "2_2") (pintype "passive"))
      (node (ref "DUE") (pin "5V0@0") (pinfunction "5V0_5V0@0") (pintype "passive"))
      (node (ref "DUE") (pin "5V0@1") (pinfunction "5V0_5V0@1") (pintype "passive"))
      (node (ref "DUE") (pin "5V0@2") (pinfunction "5V0_5V0@2") (pintype "passive"))
      (node (ref "DUE") (pin "5V0@3") (pinfunction "5V0_5V0@3") (pintype "passive"))
      (node (ref "I2C_5V") (pin "2") (pinfunction "+5_2") (pintype "passive"))
      (node (ref "LCD") (pin "2") (pinfunction "VCC_2") (pintype "passive"))
      (node (ref "Q1") (pin "2") (pinfunction "S_2") (pintype "passive"))
      (node (ref "R1") (pin "1") (pinfunction "1_1") (pintype "passive"))
      (node (ref "R13") (pin "1") (pinfunction "1_1") (pintype "passive"))
      (node (ref "R3") (pin "2") (pinfunction "2_2") (pintype "passive"))
      (node (ref "R4") (pin "2") (pinfunction "2_2") (pintype "passive"))
      (node (ref "RELAY1") (pin "1") (pinfunction "1_1") (pintype "passive"))
      (node (ref "RELAY2") (pin "1") (pinfunction "1_1") (pintype "passive"))
      (node (ref "RELAY3") (pin "1") (pinfunction "1_1") (pintype "passive"))
      (node (ref "T1") (pin "3") (pinfunction "+5V_3") (pintype "passive"))
      (node (ref "T2") (pin "3") (pinfunction "+5V_3") (pintype "passive"))
      (node (ref "TP1") (pin "3") (pinfunction "+5V_3") (pintype "passive"))
      (node (ref "U2") (pin "1") (pinfunction "VCC_1") (pintype "passive"))
      (node (ref "U3") (pin "1") (pinfunction "VCC_1") (pintype "passive"))
      (node (ref "U3") (pin "8") (pinfunction "AD0_8") (pintype "passive"))
      (node (ref "U5") (pin "7") (pinfunction "VCC_7") (pintype "passive"))
      (node (ref "U9") (pin "3") (pinfunction "IN_3") (pintype "passive"))
    )
    (net (code "4") (name "/AREF") (class "Default")
      (node (ref "AREF=3.3V") (pin "2") (pinfunction "2_2") (pintype "passive"))
      (node (ref "C3") (pin "1") (pinfunction "1_1") (pintype "passive"))
      (node (ref "DUE") (pin "AREF") (pinfunction "AREF_AREF") (pintype "passive"))
      (node (ref "U1") (pin "5") (pinfunction "VOUT_SENSE_5") (pintype "passive"))
      (node (ref "U1") (pin "6") (pinfunction "VOUT_FORCE_6") (pintype "passive"))
      (node (ref "U1-2") (pin "2") (pinfunction "OUT_2") (pintype "passive"))
    )
    (net (code "5") (name "/ETH-CS") (class "Default")
      (node (ref "DUE") (pin "10") (pinfunction "10_10") (pintype "passive"))
      (node (ref "NET") (pin "5") (pinfunction "CS_5") (pintype "passive"))
    )
    (net (code "6") (name "/ETH-RST") (class "Default")
      (node (ref "DUE") (pin "8") (pinfunction "8_8") (pintype "passive"))
      (node (ref "NET") (pin "8") (pinfunction "RST_8") (pintype "passive"))
    )
    (net (code "7") (name "/FLASH-CS") (class "Default")
      (node (ref "DUE") (pin "22") (pinfunction "22_22") (pintype "passive"))
      (node (ref "U7") (pin "1") (pinfunction "CS#_1") (pintype "passive"))
    )
    (net (code "8") (name "/GND") (class "Default")
      (node (ref "B1") (pin "2") (pinfunction "2_2") (pintype "passive"))
      (node (ref "C1") (pin "2") (pinfunction "2_2") (pintype "passive"))
      (node (ref "C10") (pin "1") (pinfunction "1_1") (pintype "passive"))
      (node (ref "C12") (pin "2") (pinfunction "2_2") (pintype "passive"))
      (node (ref "C13") (pin "1") (pinfunction "1_1") (pintype "passive"))
      (node (ref "C14") (pin "1") (pinfunction "1_1") (pintype "passive"))
      (node (ref "C15") (pin "1") (pinfunction "1_1") (pintype "passive"))
      (node (ref "C16") (pin "2") (pinfunction "2_2") (pintype "passive"))
      (node (ref "C17") (pin "1") (pinfunction "1_1") (pintype "passive"))
      (node (ref "C18") (pin "1") (pinfunction "1_1") (pintype "passive"))
      (node (ref "C19") (pin "1") (pinfunction "1_1") (pintype "passive"))
      (node (ref "C2") (pin "2") (pinfunction "2_2") (pintype "passive"))
      (node (ref "C20") (pin "1") (pinfunction "1_1") (pintype "passive"))
      (node (ref "C21") (pin "1") (pinfunction "1_1") (pintype "passive"))
      (node (ref "C22") (pin "1") (pinfunction "1_1") (pintype "passive"))
      (node (ref "C23") (pin "1") (pinfunction "1_1") (pintype "passive"))
      (node (ref "C24") (pin "1") (pinfunction "1_1") (pintype "passive"))
      (node (ref "C25") (pin "1") (pinfunction "1_1") (pintype "passive"))
      (node (ref "C3") (pin "2") (pinfunction "2_2") (pintype "passive"))
      (node (ref "C30") (pin "1") (pinfunction "1_1") (pintype "passive"))
      (node (ref "C31") (pin "1") (pinfunction "1_1") (pintype "passive"))
      (node (ref "C32") (pin "1") (pinfunction "1_1") (pintype "passive"))
      (node (ref "C33") (pin "1") (pinfunction "1_1") (pintype "passive"))
      (node (ref "C4") (pin "1") (pinfunction "1_1") (pintype "passive"))
      (node (ref "C5") (pin "2") (pinfunction "2_2") (pintype "passive"))
      (node (ref "C6") (pin "2") (pinfunction "2_2") (pintype "passive"))
      (node (ref "C7") (pin "2") (pinfunction "2_2") (pintype "passive"))
      (node (ref "C8") (pin "2") (pinfunction "2_2") (pintype "passive"))
      (node (ref "C9") (pin "1") (pinfunction "1_1") (pintype "passive"))
      (node (ref "D1") (pin "3") (pinfunction "3_3") (pintype "passive"))
      (node (ref "D10") (pin "1") (pinfunction "1_1") (pintype "passive"))
      (node (ref "D11") (pin "1") (pinfunction "1_1") (pintype "passive"))
      (node (ref "D2") (pin "3") (pinfunction "3_3") (pintype "passive"))
      (node (ref "D4") (pin "1") (pinfunction "A_1") (pintype "passive"))
      (node (ref "D5") (pin "1") (pinfunction "A_1") (pintype "passive"))
      (node (ref "D6") (pin "1") (pinfunction "A_1") (pintype "passive"))
      (node (ref "D7") (pin "1") (pinfunction "A_1") (pintype "passive"))
      (node (ref "D8") (pin "1") (pinfunction "A_1") (pintype "passive"))
      (node (ref "D9") (pin "1") (pinfunction "A_1") (pintype "passive"))
      (node (ref "DUE") (pin "GND@0") (pinfunction "GND_GND@0") (pintype "passive"))
      (node (ref "DUE") (pin "GND@1") (pinfunction "GND_GND@1") (pintype "passive"))
      (node (ref "DUE") (pin "GND@2") (pinfunction "GND_GND@2") (pintype "passive"))
      (node (ref "DUE") (pin "GND@3") (pinfunction "GND_GND@3") (pintype "passive"))
      (node (ref "DUE") (pin "GND@4") (pinfunction "GND_GND@4") (pintype "passive"))
      (node (ref "DUE") (pin "GND@5") (pinfunction "GND_GND@5") (pintype "passive"))
      (node (ref "GND") (pin "1") (pinfunction "GND_1") (pintype "passive"))
      (node (ref "GND") (pin "2") (pinfunction "DQ_2") (pintype "passive"))
      (node (ref "GND") (pin "3") (pinfunction "+5V_3") (pintype "passive"))
      (node (ref "GND_") (pin "1") (pinfunction "GND_1") (pintype "passive"))
      (node (ref "GND_") (pin "2") (pinfunction "DQ_2") (pintype "passive"))
      (node (ref "GND_") (pin "3") (pinfunction "+5V_3") (pintype "passive"))
      (node (ref "I2C1_3.3V") (pin "1") (pinfunction "G_1") (pintype "passive"))
      (node (ref "I2C_3.3V") (pin "1") (pinfunction "G_1") (pintype "passive"))
      (node (ref "I2C_5V") (pin "1") (pinfunction "G_1") (pintype "passive"))
      (node (ref "INA1") (pin "1") (pinfunction "1_1") (pintype "passive"))
      (node (ref "INA2") (pin "1") (pinfunction "1_1") (pintype "passive"))
      (node (ref "INA3") (pin "1") (pinfunction "1_1") (pintype "passive"))
      (node (ref "INA4") (pin "1") (pinfunction "1_1") (pintype "passive"))
      (node (ref "INA4-20_1") (pin "1") (pinfunction "1_1") (pintype "passive"))
      (node (ref "INA4-20_2") (pin "1") (pinfunction "1_1") (pintype "passive"))
      (node (ref "KEYS") (pin "1") (pinfunction "GND_1") (pintype "passive"))
      (node (ref "LCD") (pin "1") (pinfunction "GND_1") (pintype "passive"))
      (node (ref "MICRO-SD") (pin "10") (pinfunction "GND_10") (pintype "passive"))
      (node (ref "MICRO-SD") (pin "11") (pinfunction "GND_11") (pintype "passive"))
      (node (ref "MICRO-SD") (pin "12") (pinfunction "GND_12") (pintype "passive"))
      (node (ref "MICRO-SD") (pin "13") (pinfunction "GND_13") (pintype "passive"))
      (node (ref "MICRO-SD") (pin "6") (pinfunction "VSS_6") (pintype "passive"))
      (node (ref "NET") (pin "1") (pinfunction "GND_1") (pintype "passive"))
      (node (ref "NET") (pin "12") (pinfunction "GND_12") (pintype "passive"))
      (node (ref "NET") (pin "2") (pinfunction "GND_2") (pintype "passive"))
      (node (ref "OUTA1") (pin "1") (pinfunction "1_1") (pintype "passive"))
      (node (ref "OUTA2") (pin "1") (pinfunction "1_1") (pintype "passive"))
      (node (ref "PWMO2") (pin "1") (pinfunction "GND_1") (pintype "passive"))
      (node (ref "Q4") (pin "2") (pinfunction "E_2") (pintype "passive"))
      (node (ref "R1") (pin "3") (pinfunction "3_3") (pintype "passive"))
      (node (ref "R12") (pin "1") (pinfunction "1_1") (pintype "passive"))
      (node (ref "R14") (pin "2") (pinfunction "2_2") (pintype "passive"))
      (node (ref "R15") (pin "1") (pinfunction "1_1") (pintype "passive"))
      (node (ref "R16") (pin "1") (pinfunction "1_1") (pintype "passive"))
      (node (ref "R21") (pin "1") (pinfunction "1_1") (pintype "passive"))
      (node (ref "R22") (pin "1") (pinfunction "1_1") (pintype "passive"))
      (node (ref "R23") (pin "1") (pinfunction "1_1") (pintype "passive"))
      (node (ref "R29") (pin "1") (pinfunction "1_1") (pintype "passive"))
      (node (ref "R30") (pin "1") (pinfunction "1_1") (pintype "passive"))
      (node (ref "R45") (pin "1") (pinfunction "1_1") (pintype "passive"))
      (node (ref "R6") (pin "1") (pinfunction "1_1") (pintype "passive"))
      (node (ref "R8") (pin "1") (pinfunction "1_1") (pintype "passive"))
      (node (ref "RELAY1") (pin "2") (pinfunction "2_2") (pintype "passive"))
      (node (ref "RELAY2") (pin "2") (pinfunction "2_2") (pintype "passive"))
      (node (ref "RELAY3") (pin "2") (pinfunction "2_2") (pintype "passive"))
      (node (ref "SER1") (pin "1") (pinfunction "G_1") (pintype "passive"))
      (node (ref "SER2") (pin "1") (pinfunction "G_1") (pintype "passive"))
      (node (ref "SER3") (pin "1") (pinfunction "G_1") (pintype "passive"))
      (node (ref "SER4") (pin "1") (pinfunction "G_1") (pintype "passive"))
      (node (ref "U1") (pin "1") (pinfunction "GND_FORCE_1") (pintype "passive"))
      (node (ref "U1") (pin "2") (pinfunction "GND_SENSE_2") (pintype "passive"))
      (node (ref "U1-2") (pin "3") (pinfunction "GND_3") (pintype "passive"))
      (node (ref "U10") (pin "4") (pinfunction "GND_4") (pintype "passive"))
      (node (ref "U11") (pin "3") (pinfunction "EM_3") (pintype "passive"))
      (node (ref "U12") (pin "3") (pinfunction "EM_3") (pintype "passive"))
      (node (ref "U13") (pin "3") (pinfunction "EM_3") (pintype "passive"))
      (node (ref "U14") (pin "3") (pinfunction "EM_3") (pintype "passive"))
      (node (ref "U15") (pin "3") (pinfunction "EM_3") (pintype "passive"))
      (node (ref "U16") (pin "3") (pinfunction "EM_3") (pintype "passive"))
      (node (ref "U17") (pin "2") (pinfunction "-Vin_2") (pintype "passive"))
      (node (ref "U18") (pin "2") (pinfunction "CA_2") (pintype "passive"))
      (node (ref "U19") (pin "2") (pinfunction "CA_2") (pintype "passive"))
      (node (ref "U2") (pin "3") (pinfunction "GND_3") (pintype "passive"))
      (node (ref "U2") (pin "7") (pinfunction "AD1_7") (pintype "passive"))
      (node (ref "U2") (pin "8") (pinfunction "AD0_8") (pintype "passive"))
      (node (ref "U20") (pin "3") (pinfunction "3_3") (pintype "passive"))
      (node (ref "U3") (pin "3") (pinfunction "GND_3") (pintype "passive"))
      (node (ref "U3") (pin "7") (pinfunction "AD1_7") (pintype "passive"))
      (node (ref "U4") (pin "5") (pinfunction "GND_5") (pintype "passive"))
      (node (ref "U5") (pin "2") (pinfunction "GND_2") (pintype "passive"))
      (node (ref "U6") (pin "8") (pinfunction "E_8") (pintype "passive"))
      (node (ref "U7") (pin "4") (pinfunction "GND_4") (pintype "passive"))
      (node (ref "U8") (pin "2") (pinfunction "E1_2") (pintype "passive"))
      (node (ref "U8") (pin "3") (pinfunction "E2_3") (pintype "passive"))
      (node (ref "U8") (pin "4") (pinfunction "VSS_4") (pintype "passive"))
      (node (ref "U8") (pin "7") (pinfunction "WC#_7") (pintype "passive"))
      (node (ref "U9") (pin "1") (pinfunction "ADJ/GND_1") (pintype "passive"))
    )
    (net (code "9") (name "/IN_A1") (class "Default")
      (node (ref "C20") (pin "2") (pinfunction "2_2") (pintype "passive"))
      (node (ref "D6") (pin "3") (pinfunction "A/C_3") (pintype "passive"))
      (node (ref "DUE") (pin "A2") (pinfunction "A2_A2") (pintype "passive"))
      (node (ref "R21") (pin "2") (pinfunction "2_2") (pintype "passive"))
    )
    (net (code "10") (name "/IN_A2") (class "Default")
      (node (ref "C21") (pin "2") (pinfunction "2_2") (pintype "passive"))
      (node (ref "D7") (pin "3") (pinfunction "A/C_3") (pintype "passive"))
      (node (ref "DUE") (pin "A3") (pinfunction "A3_A3") (pintype "passive"))
      (node (ref "R22") (pin "2") (pinfunction "2_2") (pintype "passive"))
    )
    (net (code "11") (name "/IN_A3") (class "Default")
      (node (ref "C22") (pin "2") (pinfunction "2_2") (pintype "passive"))
      (node (ref "D8") (pin "3") (pinfunction "A/C_3") (pintype "passive"))
      (node (ref "DUE") (pin "A4") (pinfunction "A4_A4") (pintype "passive"))
      (node (ref "R23") (pin "2") (pinfunction "2_2") (pintype "passive"))
    )
    (net (code "12") (name "/IN_A4") (class "Default")
      (node (ref "C23") (pin "2") (pinfunction "2_2") (pintype "passive"))
      (node (ref "D9") (pin "3") (pinfunction "A/C_3") (pintype "passive"))
      (node (ref "DUE") (pin "A5") (pinfunction "A5_A5") (pintype "passive"))
      (node (ref "R45") (pin "2") (pinfunction "2_2") (pintype "passive"))
    )
    (net (code "13") (name "/IN_A4-20mA_1") (class "Default")
      (node (ref "C18") (pin "2") (pinfunction "2_2") (pintype "passive"))
      (node (ref "D4") (pin "3") (pinfunction "A/C_3") (pintype "passive"))
      (node (ref "DUE") (pin "A0") (pinfunction "A0_A0") (pintype "passive"))
      (node (ref "INA4-20_1") (pin "2") (pinfunction "2_2") (pintype "passive"))
      (node (ref "R29") (pin "2") (pinfunction "2_2") (pintype "passive"))
    )
    (net (code "14") (name "/IN_A4-20mA_2") (class "Default")
      (node (ref "C19") (pin "2") (pinfunction "2_2") (pintype "passive"))
      (node (ref "D5") (pin "3") (pinfunction "A/C_3") (pintype "passive"))
      (node (ref "DUE") (pin "A1") (pinfunction "A1_A1") (pintype "passive"))
      (node (ref "INA4-20_2") (pin "2") (pinfunction "2_2") (pintype "passive"))
      (node (ref "R30") (pin "2") (pinfunction "2_2") (pintype "passive"))
    )
    (net (code "15") (name "/IN_P1") (class "Default")
      (node (ref "DUE") (pin "A6") (pinfunction "A6_A6") (pintype "passive"))
      (node (ref "R41") (pin "1") (pinfunction "1_1") (pintype "passive"))
      (node (ref "U11") (pin "4") (pinfunction "COL_4") (pintype "passive"))
    )
    (net (code "16") (name "/IN_P2") (class "Default")
      (node (ref "DUE") (pin "A7") (pinfunction "A7_A7") (pintype "passive"))
      (node (ref "R25") (pin "1") (pinfunction "1_1") (pintype "passive"))
      (node (ref "U12") (pin "4") (pinfunction "COL_4") (pintype "passive"))
    )
    (net (code "17") (name "/IN_P3") (class "Default")
      (node (ref "DUE") (pin "A8") (pinfunction "A8_A8") (pintype "passive"))
      (node (ref "R27") (pin "1") (pinfunction "1_1") (pintype "passive"))
      (node (ref "U13") (pin "4") (pinfunction "COL_4") (pintype "passive"))
    )
    (net (code "18") (name "/IN_P4") (class "Default")
      (node (ref "DUE") (pin "A9") (pinfunction "A9_A9") (pintype "passive"))
      (node (ref "R36") (pin "1") (pinfunction "1_1") (pintype "passive"))
      (node (ref "U14") (pin "4") (pinfunction "COL_4") (pintype "passive"))
    )
    (net (code "19") (name "/IN_P5") (class "Default")
      (node (ref "DUE") (pin "A10") (pinfunction "A10_A10") (pintype "passive"))
      (node (ref "R38") (pin "1") (pinfunction "1_1") (pintype "passive"))
      (node (ref "U15") (pin "4") (pinfunction "COL_4") (pintype "passive"))
    )
    (net (code "20") (name "/IN_P6") (class "Default")
      (node (ref "DUE") (pin "38") (pinfunction "38_38") (pintype "passive"))
      (node (ref "R40") (pin "1") (pinfunction "1_1") (pintype "passive"))
      (node (ref "U16") (pin "4") (pinfunction "COL_4") (pintype "passive"))
    )
    (net (code "21") (name "/IS_5V") (class "Default")
      (node (ref "C26") (pin "1") (pinfunction "1_1") (pintype "passive"))
      (node (ref "INP1") (pin "3") (pinfunction "+5V_3") (pintype "passive"))
      (node (ref "INP2") (pin "3") (pinfunction "+5V_3") (pintype "passive"))
      (node (ref "INP3") (pin "3") (pinfunction "+5V_3") (pintype "passive"))
      (node (ref "INP4C") (pin "3") (pinfunction "+5V_3") (pintype "passive"))
      (node (ref "INP5C") (pin "3") (pinfunction "+5V_3") (pintype "passive"))
      (node (ref "INP6C") (pin "3") (pinfunction "+5V_3") (pintype "passive"))
      (node (ref "IS+5V") (pin "1") (pinfunction "1_1") (pintype "passive"))
      (node (ref "IS+5V") (pin "2") (pinfunction "2_2") (pintype "passive"))
      (node (ref "IS+5V") (pin "3") (pinfunction "3_3") (pintype "passive"))
      (node (ref "R48") (pin "2") (pinfunction "2_2") (pintype "passive"))
      (node (ref "U17") (pin "7") (pinfunction "+Vout_7") (pintype "passive"))
    )
    (net (code "22") (name "/LCD_D4") (class "Default")
      (node (ref "DUE") (pin "25") (pinfunction "25_25") (pintype "passive"))
      (node (ref "LCD") (pin "6") (pinfunction "D4_6") (pintype "passive"))
    )
    (net (code "23") (name "/LCD_D5") (class "Default")
      (node (ref "DUE") (pin "26") (pinfunction "26_26") (pintype "passive"))
      (node (ref "LCD") (pin "7") (pinfunction "D5_7") (pintype "passive"))
    )
    (net (code "24") (name "/LCD_D6") (class "Default")
      (node (ref "DUE") (pin "27") (pinfunction "27_27") (pintype "passive"))
      (node (ref "LCD") (pin "8") (pinfunction "D6_8") (pintype "passive"))
    )
    (net (code "25") (name "/LCD_D7") (class "Default")
      (node (ref "DUE") (pin "28") (pinfunction "28_28") (pintype "passive"))
      (node (ref "LCD") (pin "9") (pinfunction "D7_9") (pintype "passive"))
    )
    (net (code "26") (name "/LCD_E") (class "Default")
      (node (ref "DUE") (pin "24") (pinfunction "24_24") (pintype "passive"))
      (node (ref "LCD") (pin "5") (pinfunction "E_5") (pintype "passive"))
    )
    (net (code "27") (name "/LCD_RS") (class "Default")
      (node (ref "DUE") (pin "23") (pinfunction "23_23") (pintype "passive"))
      (node (ref "LCD") (pin "4") (pinfunction "RS_4") (pintype "passive"))
    )
    (net (code "28") (name "/MISO") (class "Default")
      (node (ref "DUE") (pin "ICSP_MISO") (pinfunction "ICSP_MISO_ICSP_MISO") (pintype "passive"))
      (node (ref "MICRO-SD") (pin "7") (pinfunction "DAT0(D0)_7") (pintype "passive"))
      (node (ref "NET") (pin "7") (pinfunction "MISO_7") (pintype "passive"))
      (node (ref "U7") (pin "2") (pinfunction "SO/SIO1_2") (pintype "passive"))
    )
    (net (code "29") (name "/MOSI") (class "Default")
      (node (ref "DUE") (pin "ICSP_MOSI") (pinfunction "ICSP_MOSI_ICSP_MOSI") (pintype "passive"))
      (node (ref "MICRO-SD") (pin "3") (pinfunction "CMD(DI)_3") (pintype "passive"))
      (node (ref "NET") (pin "3") (pinfunction "MOSI_3") (pintype "passive"))
      (node (ref "U7") (pin "5") (pinfunction "SI/SIO0_5") (pintype "passive"))
    )
    (net (code "30") (name "/OUT_A1") (class "Default")
      (node (ref "DUE") (pin "2") (pinfunction "2_2") (pintype "passive"))
      (node (ref "R20") (pin "1") (pinfunction "1_1") (pintype "passive"))
    )
    (net (code "31") (name "/OUT_A2") (class "Default")
      (node (ref "DUE") (pin "3") (pinfunction "3_3") (pintype "passive"))
      (node (ref "R19") (pin "2") (pinfunction "2_2") (pintype "passive"))
    )
    (net (code "32") (name "/PWM_O1") (class "Default")
      (node (ref "DUE") (pin "5") (pinfunction "5_5") (pintype "passive"))
      (node (ref "R47") (pin "1") (pinfunction "1_1") (pintype "passive"))
    )
    (net (code "33") (name "/PWM_O2") (class "Default")
      (node (ref "DUE") (pin "6") (pinfunction "6_6") (pintype "passive"))
      (node (ref "PWMO2") (pin "2") (pinfunction "2_2") (pintype "passive"))
    )
    (net (code "34") (name "/PWM_O3") (class "Default")
      (node (ref "DUE") (pin "7") (pinfunction "7_7") (pintype "passive"))
      (node (ref "PWMO2") (pin "3") (pinfunction "3_3") (pintype "passive"))
    )
    (net (code "35") (name "/PWM_O4") (class "Default")
      (node (ref "DUE") (pin "9") (pinfunction "9_9") (pintype "passive"))
      (node (ref "PWMO2") (pin "4") (pinfunction "4_4") (pintype "passive"))
    )
    (net (code "36") (name "/REL1") (class "Default")
      (node (ref "DUE") (pin "39") (pinfunction "39_39") (pintype "passive"))
      (node (ref "RELAY1") (pin "3") (pinfunction "3_3") (pintype "passive"))
    )
    (net (code "37") (name "/REL2") (class "Default")
      (node (ref "DUE") (pin "40") (pinfunction "40_40") (pintype "passive"))
      (node (ref "RELAY1") (pin "4") (pinfunction "4_4") (pintype "passive"))
    )
    (net (code "38") (name "/REL3") (class "Default")
      (node (ref "DUE") (pin "41") (pinfunction "41_41") (pintype "passive"))
      (node (ref "RELAY1") (pin "5") (pinfunction "5_5") (pintype "passive"))
    )
    (net (code "39") (name "/REL4") (class "Default")
      (node (ref "DUE") (pin "42") (pinfunction "42_42") (pintype "passive"))
      (node (ref "RELAY1") (pin "6") (pinfunction "6_6") (pintype "passive"))
    )
    (net (code "40") (name "/REL5") (class "Default")
      (node (ref "DUE") (pin "44") (pinfunction "44_44") (pintype "passive"))
      (node (ref "RELAY2") (pin "6") (pinfunction "6_6") (pintype "passive"))
    )
    (net (code "41") (name "/REL6") (class "Default")
      (node (ref "DUE") (pin "45") (pinfunction "45_45") (pintype "passive"))
      (node (ref "RELAY2") (pin "5") (pinfunction "5_5") (pintype "passive"))
    )
    (net (code "42") (name "/REL7") (class "Default")
      (node (ref "DUE") (pin "46") (pinfunction "46_46") (pintype "passive"))
      (node (ref "RELAY2") (pin "4") (pinfunction "4_4") (pintype "passive"))
    )
    (net (code "43") (name "/REL8") (class "Default")
      (node (ref "DUE") (pin "47") (pinfunction "47_47") (pintype "passive"))
      (node (ref "RELAY2") (pin "3") (pinfunction "3_3") (pintype "passive"))
    )
    (net (code "44") (name "/REL9") (class "Default")
      (node (ref "DUE") (pin "48") (pinfunction "48_48") (pintype "passive"))
      (node (ref "RELAY3") (pin "3") (pinfunction "3_3") (pintype "passive"))
    )
    (net (code "45") (name "/REL10") (class "Default")
      (node (ref "DUE") (pin "49") (pinfunction "49_49") (pintype "passive"))
      (node (ref "RELAY3") (pin "4") (pinfunction "4_4") (pintype "passive"))
    )
    (net (code "46") (name "/REL11") (class "Default")
      (node (ref "DUE") (pin "50") (pinfunction "50_50") (pintype "passive"))
      (node (ref "RELAY3") (pin "5") (pinfunction "5_5") (pintype "passive"))
    )
    (net (code "47") (name "/REL12") (class "Default")
      (node (ref "DUE") (pin "51") (pinfunction "51_51") (pintype "passive"))
      (node (ref "RELAY3") (pin "6") (pinfunction "6_6") (pintype "passive"))
    )
    (net (code "48") (name "/RELDC1") (class "Default")
      (node (ref "DUE") (pin "36") (pinfunction "36_36") (pintype "passive"))
      (node (ref "R43") (pin "1") (pinfunction "1_1") (pintype "passive"))
    )
    (net (code "49") (name "/RELDC2") (class "Default")
      (node (ref "DUE") (pin "37") (pinfunction "37_37") (pintype "passive"))
      (node (ref "R44") (pin "1") (pinfunction "1_1") (pintype "passive"))
    )
    (net (code "50") (name "/RXD1") (class "Default")
      (node (ref "DUE") (pin "15") (pinfunction "(RX1)15_15") (pintype "passive"))
      (node (ref "SER1") (pin "2") (pinfunction "RX_2") (pintype "passive"))
    )
    (net (code "51") (name "/RXD2") (class "Default")
      (node (ref "DUE") (pin "17") (pinfunction "(RX2)17_17") (pintype "passive"))
      (node (ref "SER2") (pin "2") (pinfunction "RX_2") (pintype "passive"))
    )
    (net (code "52") (name "/RXD3") (class "Default")
      (node (ref "DUE") (pin "19") (pinfunction "(RX3)19_19") (pintype "passive"))
      (node (ref "SER3") (pin "2") (pinfunction "RX_2") (pintype "passive"))
    )
    (net (code "53") (name "/RXD4") (class "Default")
      (node (ref "DUE") (pin "52") (pinfunction "52(CAN1_RX)_52") (pintype "passive"))
      (node (ref "SER4") (pin "2") (pinfunction "RX_2") (pintype "passive"))
    )
    (net (code "54") (name "/SCL") (class "Default")
      (node (ref "DUE") (pin "21") (pinfunction "(I2C0_SCL)21_21") (pintype "passive"))
      (node (ref "I2C_3.3V") (pin "4") (pinfunction "SCL_4") (pintype "passive"))
      (node (ref "U4") (pin "8") (pinfunction "SCL_8") (pintype "passive"))
      (node (ref "U5") (pin "5") (pinfunction "VL1_5") (pintype "passive"))
      (node (ref "U8") (pin "6") (pinfunction "SCL_6") (pintype "passive"))
    )
    (net (code "55") (name "/SCL1") (class "Default")
      (node (ref "DUE") (pin "SCL1") (pinfunction "I2C1_SCL_SCL1") (pintype "passive"))
      (node (ref "I2C1_3.3V") (pin "4") (pinfunction "SCL_4") (pintype "passive"))
      (node (ref "R49") (pin "2") (pinfunction "2_2") (pintype "passive"))
    )
    (net (code "56") (name "/SCLK") (class "Default")
      (node (ref "DUE") (pin "ICSP_SCK") (pinfunction "ICSP_SCK_ICSP_SCK") (pintype "passive"))
      (node (ref "MICRO-SD") (pin "5") (pinfunction "CLK(SCLK)_5") (pintype "passive"))
      (node (ref "NET") (pin "4") (pinfunction "SCLK_4") (pintype "passive"))
      (node (ref "U7") (pin "6") (pinfunction "SCLK_6") (pintype "passive"))
    )
    (net (code "57") (name "/SD-CS") (class "Default")
      (node (ref "DUE") (pin "4") (pinfunction "4_4") (pintype "passive"))
      (node (ref "MICRO-SD") (pin "2") (pinfunction "CDDAT3(CS)_2") (pintype "passive"))
    )
    (net (code "58") (name "/SDA") (class "Default")
      (node (ref "DUE") (pin "20") (pinfunction "(I2C0_SDA)20_20") (pintype "passive"))
      (node (ref "I2C_3.3V") (pin "3") (pinfunction "SDA_3") (pintype "passive"))
      (node (ref "U4") (pin "7") (pinfunction "SDA_7") (pintype "passive"))
      (node (ref "U5") (pin "4") (pinfunction "VL2_4") (pintype "passive"))
      (node (ref "U8") (pin "5") (pinfunction "SDA_5") (pintype "passive"))
    )
    (net (code "59") (name "/SDA1") (class "Default")
      (node (ref "DUE") (pin "SDA1") (pinfunction "I2C1_SDA_SDA1") (pintype "passive"))
      (node (ref "I2C1_3.3V") (pin "3") (pinfunction "SDA_3") (pintype "passive"))
      (node (ref "R50") (pin "2") (pinfunction "2_2") (pintype "passive"))
    )
    (net (code "60") (name "/TXD1") (class "Default")
      (node (ref "DUE") (pin "14") (pinfunction "(TX1)14_14") (pintype "passive"))
      (node (ref "SER1") (pin "3") (pinfunction "TX_3") (pintype "passive"))
    )
    (net (code "61") (name "/TXD2") (class "Default")
      (node (ref "DUE") (pin "16") (pinfunction "(TX2)16_16") (pintype "passive"))
      (node (ref "SER2") (pin "3") (pinfunction "TX_3") (pintype "passive"))
    )
    (net (code "62") (name "/TXD3") (class "Default")
      (node (ref "DUE") (pin "18") (pinfunction "(TX3)18_18") (pintype "passive"))
      (node (ref "SER3") (pin "3") (pinfunction "TX_3") (pintype "passive"))
    )
    (net (code "63") (name "/TXD4") (class "Default")
      (node (ref "DUE") (pin "A11") (pinfunction "A11_A11") (pintype "passive"))
      (node (ref "SER4") (pin "3") (pinfunction "TX_3") (pintype "passive"))
    )
    (net (code "64") (name "/ULN1") (class "Default")
      (node (ref "DUE") (pin "29") (pinfunction "29_29") (pintype "passive"))
      (node (ref "U6") (pin "1") (pinfunction "1B_1") (pintype "passive"))
    )
    (net (code "65") (name "/ULN2") (class "Default")
      (node (ref "DUE") (pin "30") (pinfunction "30_30") (pintype "passive"))
      (node (ref "U6") (pin "2") (pinfunction "2B_2") (pintype "passive"))
    )
    (net (code "66") (name "/ULN3") (class "Default")
      (node (ref "DUE") (pin "31") (pinfunction "31_31") (pintype "passive"))
      (node (ref "U6") (pin "3") (pinfunction "3B_3") (pintype "passive"))
    )
    (net (code "67") (name "/ULN4") (class "Default")
      (node (ref "DUE") (pin "32") (pinfunction "32_32") (pintype "passive"))
      (node (ref "U6") (pin "4") (pinfunction "4B_4") (pintype "passive"))
    )
    (net (code "68") (name "/ULN5") (class "Default")
      (node (ref "DUE") (pin "33") (pinfunction "33_33") (pintype "passive"))
      (node (ref "U6") (pin "5") (pinfunction "5B_5") (pintype "passive"))
    )
    (net (code "69") (name "/ULN6") (class "Default")
      (node (ref "DUE") (pin "34") (pinfunction "34_34") (pintype "passive"))
      (node (ref "U6") (pin "6") (pinfunction "6B_6") (pintype "passive"))
    )
    (net (code "70") (name "/ULN7") (class "Default")
      (node (ref "DUE") (pin "35") (pinfunction "35_35") (pintype "passive"))
      (node (ref "U6") (pin "7") (pinfunction "7B_7") (pintype "passive"))
    )
    (net (code "71") (name "/VIN(12V)") (class "Default")
      (node (ref "+12V") (pin "1") (pinfunction "GND_1") (pintype "passive"))
      (node (ref "+12V") (pin "2") (pinfunction "DQ_2") (pintype "passive"))
      (node (ref "+12V") (pin "3") (pinfunction "+5V_3") (pintype "passive"))
      (node (ref "BUZZER-12V") (pin "1") (pinfunction "+_1") (pintype "passive"))
      (node (ref "C15") (pin "2") (pinfunction "2_2") (pintype "passive"))
      (node (ref "C24") (pin "2") (pinfunction "2_2") (pintype "passive"))
      (node (ref "C25") (pin "2") (pinfunction "2_2") (pintype "passive"))
      (node (ref "DUE") (pin "VIN") (pinfunction "VIN_VIN") (pintype "passive"))
      (node (ref "L1") (pin "1") (pinfunction "1_1") (pintype "passive"))
      (node (ref "R2") (pin "1") (pinfunction "1_1") (pintype "passive"))
      (node (ref "U10") (pin "8") (pinfunction "VCC_8") (pintype "passive"))
    )
    (net (code "72") (name "Net-(DUE-(CAN1_TX)53)") (class "Default")
      (node (ref "DUE") (pin "53") (pinfunction "(CAN1_TX)53_53") (pintype "passive"))
      (node (ref "LED") (pin "2") (pinfunction "2_2") (pintype "passive"))
    )
    (net (code "73") (name "Net-(DUE-A12(DAC0))") (class "Default")
      (node (ref "DUE") (pin "A12") (pinfunction "A12(DAC0)_A12") (pintype "passive"))
      (node (ref "KEYS") (pin "2") (pinfunction "2_2") (pintype "passive"))
    )
    (net (code "74") (name "Net-(DUE-A13(DAC1))") (class "Default")
      (node (ref "DUE") (pin "A13") (pinfunction "A13(DAC1)_A13") (pintype "passive"))
      (node (ref "KEYS") (pin "3") (pinfunction "3_3") (pintype "passive"))
    )
    (net (code "75") (name "Net-(DUE-A14(CAN0_RX))") (class "Default")
      (node (ref "DUE") (pin "A14") (pinfunction "A14(CAN0_RX)_A14") (pintype "passive"))
      (node (ref "KEYS") (pin "4") (pinfunction "4_4") (pintype "passive"))
    )
    (net (code "76") (name "Net-(DUE-A15(CAN0_TX))") (class "Default")
      (node (ref "DUE") (pin "A15") (pinfunction "A15(CAN0_TX)_A15") (pintype "passive"))
      (node (ref "KEYS") (pin "5") (pinfunction "5_5") (pintype "passive"))
    )
    (net (code "77") (name "Net-(DUE-Pad11)") (class "Default")
      (node (ref "DUE") (pin "11") (pinfunction "11_11") (pintype "passive"))
      (node (ref "PWMO3") (pin "1") (pinfunction "1_1") (pintype "passive"))
    )
    (net (code "78") (name "Net-(DUE-Pad12)") (class "Default")
      (node (ref "DUE") (pin "12") (pinfunction "12_12") (pintype "passive"))
      (node (ref "PWMO3") (pin "2") (pinfunction "2_2") (pintype "passive"))
    )
    (net (code "79") (name "Net-(DUE-Pad13)") (class "Default")
      (node (ref "DUE") (pin "13") (pinfunction "13_13") (pintype "passive"))
      (node (ref "PWMO3") (pin "3") (pinfunction "3_3") (pintype "passive"))
    )
    (net (code "80") (name "Net-(DUE-Pad43)") (class "Default")
      (node (ref "DUE") (pin "43") (pinfunction "43_43") (pintype "passive"))
      (node (ref "R11") (pin "2") (pinfunction "2_2") (pintype "passive"))
    )
    (net (code "81") (name "Net-(I2C_5V-SCL)") (class "Default")
      (node (ref "I2C_5V") (pin "4") (pinfunction "SCL_4") (pintype "passive"))
      (node (ref "R4") (pin "1") (pinfunction "1_1") (pintype "passive"))
      (node (ref "U2") (pin "4") (pinfunction "SCL_4") (pintype "passive"))
      (node (ref "U3") (pin "4") (pinfunction "SCL_4") (pintype "passive"))
      (node (ref "U5") (pin "8") (pinfunction "VCC1_8") (pintype "passive"))
    )
    (net (code "82") (name "Net-(I2C_5V-SDA)") (class "Default")
      (node (ref "I2C_5V") (pin "3") (pinfunction "SDA_3") (pintype "passive"))
      (node (ref "R3") (pin "1") (pinfunction "1_1") (pintype "passive"))
      (node (ref "U2") (pin "5") (pinfunction "SDA_5") (pintype "passive"))
      (node (ref "U3") (pin "5") (pinfunction "SDA_5") (pintype "passive"))
      (node (ref "U5") (pin "1") (pinfunction "VCC2_1") (pintype "passive"))
    )
    (net (code "83") (name "Net-(INA1-Pad2)") (class "Default")
      (node (ref "INA1") (pin "2") (pinfunction "2_2") (pintype "passive"))
      (node (ref "R31") (pin "1") (pinfunction "1_1") (pintype "passive"))
    )
    (net (code "84") (name "Net-(INA2-Pad2)") (class "Default")
      (node (ref "INA2") (pin "2") (pinfunction "2_2") (pintype "passive"))
      (node (ref "R32") (pin "1") (pinfunction "1_1") (pintype "passive"))
    )
    (net (code "85") (name "Net-(INA3-Pad2)") (class "Default")
      (node (ref "INA3") (pin "2") (pinfunction "2_2") (pintype "passive"))
      (node (ref "R33") (pin "1") (pinfunction "1_1") (pintype "passive"))
    )
    (net (code "86") (name "Net-(INA4-Pad2)") (class "Default")
      (node (ref "INA4") (pin "2") (pinfunction "2_2") (pintype "passive"))
      (node (ref "R46") (pin "1") (pinfunction "1_1") (pintype "passive"))
    )
    (net (code "87") (name "Net-(INP1-DQ)") (class "Default")
      (node (ref "INP1") (pin "2") (pinfunction "DQ_2") (pintype "passive"))
      (node (ref "R42") (pin "1") (pinfunction "1_1") (pintype "passive"))
    )
    (net (code "88") (name "Net-(INP1-GND)") (class "Default")
      (node (ref "INP*.1->IS_GND") (pin "1") (pinfunction "1_1") (pintype "passive"))
      (node (ref "INP1") (pin "1") (pinfunction "GND_1") (pintype "passive"))
      (node (ref "U11") (pin "2") (pinfunction "CA_2") (pintype "passive"))
    )
    (net (code "89") (name "Net-(INP2-DQ)") (class "Default")
      (node (ref "INP2") (pin "2") (pinfunction "DQ_2") (pintype "passive"))
      (node (ref "R24") (pin "1") (pinfunction "1_1") (pintype "passive"))
    )
    (net (code "90") (name "Net-(INP2-GND)") (class "Default")
      (node (ref "INP*.1->IS_GND") (pin "2") (pinfunction "2_2") (pintype "passive"))
      (node (ref "INP2") (pin "1") (pinfunction "GND_1") (pintype "passive"))
      (node (ref "U12") (pin "2") (pinfunction "CA_2") (pintype "passive"))
    )
    (net (code "91") (name "Net-(INP3-DQ)") (class "Default")
      (node (ref "INP3") (pin "2") (pinfunction "DQ_2") (pintype "passive"))
      (node (ref "R26") (pin "1") (pinfunction "1_1") (pintype "passive"))
    )
    (net (code "92") (name "Net-(INP3-GND)") (class "Default")
      (node (ref "INP*.1->IS_GND") (pin "3") (pinfunction "3_3") (pintype "passive"))
      (node (ref "INP3") (pin "1") (pinfunction "GND_1") (pintype "passive"))
      (node (ref "U13") (pin "2") (pinfunction "CA_2") (pintype "passive"))
    )
    (net (code "93") (name "Net-(INP4C-DQ)") (class "Default")
      (node (ref "INP4C") (pin "2") (pinfunction "DQ_2") (pintype "passive"))
      (node (ref "R28") (pin "1") (pinfunction "1_1") (pintype "passive"))
    )
    (net (code "94") (name "Net-(INP4C-GND)") (class "Default")
      (node (ref "C11") (pin "2") (pinfunction "2_2") (pintype "passive"))
      (node (ref "INP*.1->IS_GND") (pin "4") (pinfunction "4_4") (pintype "passive"))
      (node (ref "INP4C") (pin "1") (pinfunction "GND_1") (pintype "passive"))
      (node (ref "U14") (pin "2") (pinfunction "CA_2") (pintype "passive"))
    )
    (net (code "95") (name "Net-(INP5C-DQ)") (class "Default")
      (node (ref "INP5C") (pin "2") (pinfunction "DQ_2") (pintype "passive"))
      (node (ref "R37") (pin "1") (pinfunction "1_1") (pintype "passive"))
    )
    (net (code "96") (name "Net-(INP5C-GND)") (class "Default")
      (node (ref "C28") (pin "2") (pinfunction "2_2") (pintype "passive"))
      (node (ref "INP*.1->IS_GND") (pin "5") (pinfunction "5_5") (pintype "passive"))
      (node (ref "INP5C") (pin "1") (pinfunction "GND_1") (pintype "passive"))
      (node (ref "U15") (pin "2") (pinfunction "CA_2") (pintype "passive"))
    )
    (net (code "97") (name "Net-(INP6C-DQ)") (class "Default")
      (node (ref "INP6C") (pin "2") (pinfunction "DQ_2") (pintype "passive"))
      (node (ref "R39") (pin "1") (pinfunction "1_1") (pintype "passive"))
    )
    (net (code "98") (name "Net-(INP6C-GND)") (class "Default")
      (node (ref "C29") (pin "2") (pinfunction "2_2") (pintype "passive"))
      (node (ref "INP*.1->IS_GND") (pin "6") (pinfunction "6_6") (pintype "passive"))
      (node (ref "INP6C") (pin "1") (pinfunction "GND_1") (pintype "passive"))
      (node (ref "U16") (pin "2") (pinfunction "CA_2") (pintype "passive"))
    )
    (net (code "99") (name "Net-(LCD-VEE)") (class "Default")
      (node (ref "LCD") (pin "3") (pinfunction "VEE_3") (pintype "passive"))
      (node (ref "R1") (pin "2") (pinfunction "2_2") (pintype "passive"))
    )
    (net (code "100") (name "Net-(LED-Pad1)") (class "Default")
      (node (ref "LED") (pin "1") (pinfunction "1_1") (pintype "passive"))
      (node (ref "R14") (pin "1") (pinfunction "1_1") (pintype "passive"))
    )
    (net (code "101") (name "Net-(PWMO1-+5V)") (class "Default")
      (node (ref "C27") (pin "2") (pinfunction "2_2") (pintype "passive"))
      (node (ref "PWMO1") (pin "3") (pinfunction "+5V_3") (pintype "passive"))
      (node (ref "U20") (pin "6") (pinfunction "6_6") (pintype "passive"))
    )
    (net (code "102") (name "Net-(PWMO1-DQ)") (class "Default")
      (node (ref "PWMO1") (pin "2") (pinfunction "DQ_2") (pintype "passive"))
      (node (ref "U20") (pin "5") (pinfunction "5_5") (pintype "passive"))
    )
    (net (code "103") (name "Net-(PWMO1-GND)") (class "Default")
      (node (ref "C27") (pin "1") (pinfunction "1_1") (pintype "passive"))
      (node (ref "PWMO1") (pin "1") (pinfunction "GND_1") (pintype "passive"))
      (node (ref "U20") (pin "4") (pinfunction "4_4") (pintype "passive"))
    )
    (net (code "104") (name "Net-(Q1-D)") (class "Default")
      (node (ref "D2") (pin "1") (pinfunction "1_1") (pintype "passive"))
      (node (ref "D2") (pin "2") (pinfunction "2_2") (pintype "passive"))
      (node (ref "Q1") (pin "3") (pinfunction "D_3") (pintype "passive"))
      (node (ref "R7") (pin "1") (pinfunction "1_1") (pintype "passive"))
      (node (ref "U3") (pin "2") (pinfunction "I0_2") (pintype "passive"))
    )
    (net (code "105") (name "Net-(Q1-G)") (class "Default")
      (node (ref "Q1") (pin "1") (pinfunction "G_1") (pintype "passive"))
      (node (ref "U3") (pin "6") (pinfunction "PCTLZ_6") (pintype "passive"))
    )
    (net (code "106") (name "Net-(Q4-B)") (class "Default")
      (node (ref "Q4") (pin "1") (pinfunction "B_1") (pintype "passive"))
      (node (ref "R11") (pin "1") (pinfunction "1_1") (pintype "passive"))
    )
    (net (code "107") (name "Net-(Q4-C)") (class "Default")
      (node (ref "BUZZER-12V") (pin "2") (pinfunction "2_2") (pintype "passive"))
      (node (ref "Q4") (pin "3") (pinfunction "C_3") (pintype "passive"))
    )
    (net (code "108") (name "Net-(R10-Pad2)") (class "Default")
      (node (ref "R10") (pin "2") (pinfunction "2_2") (pintype "passive"))
      (node (ref "R50") (pin "1") (pinfunction "1_1") (pintype "passive"))
    )
    (net (code "109") (name "Net-(R21-Pad3)") (class "Default")
      (node (ref "R21") (pin "3") (pinfunction "3_3") (pintype "passive"))
      (node (ref "R31") (pin "2") (pinfunction "2_2") (pintype "passive"))
    )
    (net (code "110") (name "Net-(R22-Pad3)") (class "Default")
      (node (ref "R22") (pin "3") (pinfunction "3_3") (pintype "passive"))
      (node (ref "R32") (pin "2") (pinfunction "2_2") (pintype "passive"))
    )
    (net (code "111") (name "Net-(R23-Pad3)") (class "Default")
      (node (ref "R23") (pin "3") (pinfunction "3_3") (pintype "passive"))
      (node (ref "R33") (pin "2") (pinfunction "2_2") (pintype "passive"))
    )
    (net (code "112") (name "Net-(R45-Pad3)") (class "Default")
      (node (ref "R45") (pin "3") (pinfunction "3_3") (pintype "passive"))
      (node (ref "R46") (pin "2") (pinfunction "2_2") (pintype "passive"))
    )
    (net (code "113") (name "Net-(R47-Pad2)") (class "Default")
      (node (ref "R47") (pin "2") (pinfunction "2_2") (pintype "passive"))
      (node (ref "U20") (pin "1") (pinfunction "1_1") (pintype "passive"))
    )
    (net (code "114") (name "Net-(R49-Pad1)") (class "Default")
      (node (ref "R49") (pin "1") (pinfunction "1_1") (pintype "passive"))
      (node (ref "R9") (pin "2") (pinfunction "2_2") (pintype "passive"))
    )
    (net (code "115") (name "Net-(T1-DQ)") (class "Default")
      (node (ref "R5") (pin "2") (pinfunction "2_2") (pintype "passive"))
      (node (ref "T1") (pin "2") (pinfunction "DQ_2") (pintype "passive"))
      (node (ref "T2") (pin "2") (pinfunction "DQ_2") (pintype "passive"))
    )
    (net (code "116") (name "Net-(T1-GND)") (class "Default")
      (node (ref "D3") (pin "3") (pinfunction "3_3") (pintype "passive"))
      (node (ref "R6") (pin "2") (pinfunction "2_2") (pintype "passive"))
      (node (ref "T1") (pin "1") (pinfunction "GND_1") (pintype "passive"))
      (node (ref "T2") (pin "1") (pinfunction "GND_1") (pintype "passive"))
    )
    (net (code "117") (name "Net-(TP1-DQ)") (class "Default")
      (node (ref "R7") (pin "2") (pinfunction "2_2") (pintype "passive"))
      (node (ref "TP1") (pin "2") (pinfunction "DQ_2") (pintype "passive"))
    )
    (net (code "118") (name "Net-(TP1-GND)") (class "Default")
      (node (ref "R8") (pin "2") (pinfunction "2_2") (pintype "passive"))
      (node (ref "TP1") (pin "1") (pinfunction "GND_1") (pintype "passive"))
    )
    (net (code "119") (name "Net-(U2-I0)") (class "Default")
      (node (ref "D1") (pin "1") (pinfunction "1_1") (pintype "passive"))
      (node (ref "D1") (pin "2") (pinfunction "2_2") (pintype "passive"))
      (node (ref "R5") (pin "1") (pinfunction "1_1") (pintype "passive"))
      (node (ref "U2") (pin "2") (pinfunction "I0_2") (pintype "passive"))
    )
    (net (code "120") (name "Net-(U4-VBAT)") (class "Default")
      (node (ref "B1") (pin "1") (pinfunction "1_1") (pintype "passive"))
      (node (ref "U4") (pin "6") (pinfunction "VBAT_6") (pintype "passive"))
    )
    (net (code "121") (name "Net-(U6-1C)") (class "Default")
      (node (ref "U6") (pin "16") (pinfunction "1C_16") (pintype "passive"))
      (node (ref "ULN(EEV)") (pin "2") (pinfunction "2_2") (pintype "passive"))
    )
    (net (code "122") (name "Net-(U6-2C)") (class "Default")
      (node (ref "U6") (pin "15") (pinfunction "2C_15") (pintype "passive"))
      (node (ref "ULN(EEV)1") (pin "1") (pinfunction "1_1") (pintype "passive"))
    )
    (net (code "123") (name "Net-(U6-3C)") (class "Default")
      (node (ref "U6") (pin "14") (pinfunction "3C_14") (pintype "passive"))
      (node (ref "ULN(EEV)1") (pin "2") (pinfunction "2_2") (pintype "passive"))
    )
    (net (code "124") (name "Net-(U6-4C)") (class "Default")
      (node (ref "U6") (pin "13") (pinfunction "4C_13") (pintype "passive"))
      (node (ref "ULN(EEV)2") (pin "1") (pinfunction "1_1") (pintype "passive"))
    )
    (net (code "125") (name "Net-(U6-5C)") (class "Default")
      (node (ref "U6") (pin "12") (pinfunction "5C_12") (pintype "passive"))
      (node (ref "ULN(EEV)2") (pin "2") (pinfunction "2_2") (pintype "passive"))
    )
    (net (code "126") (name "Net-(U6-6C)") (class "Default")
      (node (ref "U6") (pin "11") (pinfunction "6C_11") (pintype "passive"))
      (node (ref "ULN(EEV)3") (pin "1") (pinfunction "1_1") (pintype "passive"))
    )
    (net (code "127") (name "Net-(U6-7C)") (class "Default")
      (node (ref "U6") (pin "10") (pinfunction "7C_10") (pintype "passive"))
      (node (ref "ULN(EEV)3") (pin "2") (pinfunction "2_2") (pintype "passive"))
    )
    (net (code "128") (name "Net-(U6-COM)") (class "Default")
      (node (ref "C14") (pin "2") (pinfunction "2_2") (pintype "passive"))
      (node (ref "R13") (pin "2") (pinfunction "2_2") (pintype "passive"))
      (node (ref "R2") (pin "2") (pinfunction "2_2") (pintype "passive"))
      (node (ref "U6") (pin "9") (pinfunction "COM_9") (pintype "passive"))
      (node (ref "ULN(EEV)") (pin "1") (pinfunction "1_1") (pintype "passive"))
    )
    (net (code "129") (name "Net-(U7-WP#)") (class "Default")
      (node (ref "R12") (pin "2") (pinfunction "2_2") (pintype "passive"))
      (node (ref "U7") (pin "3") (pinfunction "WP#_3") (pintype "passive"))
    )
    (net (code "130") (name "Net-(U10-1IN+)") (class "Default")
      (node (ref "C17") (pin "2") (pinfunction "2_2") (pintype "passive"))
      (node (ref "R20") (pin "2") (pinfunction "2_2") (pintype "passive"))
      (node (ref "U10") (pin "3") (pinfunction "1IN+_3") (pintype "passive"))
    )
    (net (code "131") (name "Net-(U10-1IN-)") (class "Default")
      (node (ref "R16") (pin "2") (pinfunction "2_2") (pintype "passive"))
      (node (ref "R18") (pin "1") (pinfunction "1_1") (pintype "passive"))
      (node (ref "U10") (pin "2") (pinfunction "1IN-_2") (pintype "passive"))
    )
    (net (code "132") (name "Net-(U10-1OUT)") (class "Default")
      (node (ref "OUTA1") (pin "2") (pinfunction "2_2") (pintype "passive"))
      (node (ref "R18") (pin "2") (pinfunction "2_2") (pintype "passive"))
      (node (ref "U10") (pin "1") (pinfunction "1OUT_1") (pintype "passive"))
    )
    (net (code "133") (name "Net-(U10-2IN+)") (class "Default")
      (node (ref "C16") (pin "1") (pinfunction "1_1") (pintype "passive"))
      (node (ref "R19") (pin "1") (pinfunction "1_1") (pintype "passive"))
      (node (ref "U10") (pin "5") (pinfunction "2IN+_5") (pintype "passive"))
    )
    (net (code "134") (name "Net-(U10-2IN-)") (class "Default")
      (node (ref "R15") (pin "2") (pinfunction "2_2") (pintype "passive"))
      (node (ref "R17") (pin "1") (pinfunction "1_1") (pintype "passive"))
      (node (ref "U10") (pin "6") (pinfunction "2IN-_6") (pintype "passive"))
    )
    (net (code "135") (name "Net-(U10-2OUT)") (class "Default")
      (node (ref "OUTA2") (pin "2") (pinfunction "2_2") (pintype "passive"))
      (node (ref "R17") (pin "2") (pinfunction "2_2") (pintype "passive"))
      (node (ref "U10") (pin "7") (pinfunction "2OUT_7") (pintype "passive"))
    )
    (net (code "136") (name "Net-(U11-AN)") (class "Default")
      (node (ref "R42") (pin "2") (pinfunction "2_2") (pintype "passive"))
      (node (ref "U11") (pin "1") (pinfunction "AN_1") (pintype "passive"))
    )
    (net (code "137") (name "Net-(U12-AN)") (class "Default")
      (node (ref "R24") (pin "2") (pinfunction "2_2") (pintype "passive"))
      (node (ref "U12") (pin "1") (pinfunction "AN_1") (pintype "passive"))
    )
    (net (code "138") (name "Net-(U13-AN)") (class "Default")
      (node (ref "R26") (pin "2") (pinfunction "2_2") (pintype "passive"))
      (node (ref "U13") (pin "1") (pinfunction "AN_1") (pintype "passive"))
    )
    (net (code "139") (name "Net-(U14-AN)") (class "Default")
      (node (ref "C11") (pin "1") (pinfunction "1_1") (pintype "passive"))
      (node (ref "R28") (pin "2") (pinfunction "2_2") (pintype "passive"))
      (node (ref "U14") (pin "1") (pinfunction "AN_1") (pintype "passive"))
    )
    (net (code "140") (name "Net-(U15-AN)") (class "Default")
      (node (ref "C28") (pin "1") (pinfunction "1_1") (pintype "passive"))
      (node (ref "R37") (pin "2") (pinfunction "2_2") (pintype "passive"))
      (node (ref "U15") (pin "1") (pinfunction "AN_1") (pintype "passive"))
    )
    (net (code "141") (name "Net-(U16-AN)") (class "Default")
      (node (ref "C29") (pin "1") (pinfunction "1_1") (pintype "passive"))
      (node (ref "R39") (pin "2") (pinfunction "2_2") (pintype "passive"))
      (node (ref "U16") (pin "1") (pinfunction "AN_1") (pintype "passive"))
    )
    (net (code "142") (name "Net-(U17-+Vin)") (class "Default")
      (node (ref "L1") (pin "2") (pinfunction "2_2") (pintype "passive"))
      (node (ref "U17") (pin "1") (pinfunction "+Vin_1") (pintype "passive"))
    )
    (net (code "143") (name "Net-(U17--Vout)") (class "Default")
      (node (ref "C26") (pin "2") (pinfunction "2_2") (pintype "passive"))
      (node (ref "INP*.1->IS_GND") (pin "10") (pinfunction "10_10") (pintype "passive"))
      (node (ref "INP*.1->IS_GND") (pin "11") (pinfunction "11_11") (pintype "passive"))
      (node (ref "INP*.1->IS_GND") (pin "12") (pinfunction "12_12") (pintype "passive"))
      (node (ref "INP*.1->IS_GND") (pin "7") (pinfunction "7_7") (pintype "passive"))
      (node (ref "INP*.1->IS_GND") (pin "8") (pinfunction "8_8") (pintype "passive"))
      (node (ref "INP*.1->IS_GND") (pin "9") (pinfunction "9_9") (pintype "passive"))
      (node (ref "IS_GND") (pin "1") (pinfunction "1_1") (pintype "passive"))
      (node (ref "IS_GND") (pin "2") (pinfunction "2_2") (pintype "passive"))
      (node (ref "IS_GND") (pin "3") (pinfunction "3_3") (pintype "passive"))
      (node (ref "R48") (pin "1") (pinfunction "1_1") (pintype "passive"))
      (node (ref "U17") (pin "5") (pinfunction "-Vout_5") (pintype "passive"))
    )
    (net (code "144") (name "Net-(U18-AN)") (class "Default")
      (node (ref "R43") (pin "2") (pinfunction "2_2") (pintype "passive"))
      (node (ref "U18") (pin "1") (pinfunction "AN_1") (pintype "passive"))
    )
    (net (code "145") (name "Net-(U18-COL)") (class "Default")
      (node (ref "RELDC1") (pin "2") (pinfunction "2_2") (pintype "passive"))
      (node (ref "U18") (pin "4") (pinfunction "COL_4") (pintype "passive"))
    )
    (net (code "146") (name "Net-(U18-EM)") (class "Default")
      (node (ref "RELDC1") (pin "1") (pinfunction "1_1") (pintype "passive"))
      (node (ref "U18") (pin "3") (pinfunction "EM_3") (pintype "passive"))
    )
    (net (code "147") (name "Net-(U19-AN)") (class "Default")
      (node (ref "R44") (pin "2") (pinfunction "2_2") (pintype "passive"))
      (node (ref "U19") (pin "1") (pinfunction "AN_1") (pintype "passive"))
    )
    (net (code "148") (name "Net-(U19-COL)") (class "Default")
      (node (ref "RELDC2") (pin "2") (pinfunction "2_2") (pintype "passive"))
      (node (ref "U19") (pin "4") (pinfunction "COL_4") (pintype "passive"))
    )
    (net (code "149") (name "Net-(U19-EM)") (class "Default")
      (node (ref "RELDC2") (pin "1") (pinfunction "1_1") (pintype "passive"))
      (node (ref "U19") (pin "3") (pinfunction "EM_3") (pintype "passive"))
    )
    (net (code "150") (name "unconnected-(DUE-(RX0)0-Pad0)") (class "Default")
      (node (ref "DUE") (pin "0") (pinfunction "(RX0)0_0") (pintype "passive+no_connect"))
    )
    (net (code "151") (name "unconnected-(DUE-(TX0)1-Pad1)") (class "Default")
      (node (ref "DUE") (pin "1") (pinfunction "(TX0)1_1") (pintype "passive+no_connect"))
    )
    (net (code "152") (name "unconnected-(DUE-PadICSP_RESET)") (class "Default")
      (node (ref "DUE") (pin "ICSP_RESET") (pinfunction "ICSP_RESET_ICSP_RESET") (pintype "passive+no_connect"))
    )
    (net (code "153") (name "unconnected-(DUE-PadRESET)") (class "Default")
      (node (ref "DUE") (pin "RESET") (pinfunction "RESET_RESET") (pintype "passive+no_connect"))
    )
    (net (code "154") (name "unconnected-(DUE-RFU(RAW)-PadRFU)") (class "Default")
      (node (ref "DUE") (pin "RFU") (pinfunction "RFU(RAW)_RFU") (pintype "passive+no_connect"))
    )
    (net (code "155") (name "unconnected-(MICRO-SD-CD-Pad9)") (class "Default")
      (node (ref "MICRO-SD") (pin "9") (pinfunction "CD_9") (pintype "passive+no_connect"))
    )
    (net (code "156") (name "unconnected-(MICRO-SD-DAT1(RSV)-Pad8)") (class "Default")
      (node (ref "MICRO-SD") (pin "8") (pinfunction "DAT1(RSV)_8") (pintype "passive+no_connect"))
    )
    (net (code "157") (name "unconnected-(MICRO-SD-DAT2(RSV)-Pad1)") (class "Default")
      (node (ref "MICRO-SD") (pin "1") (pinfunction "DAT2(RSV)_1") (pintype "passive+no_connect"))
    )
    (net (code "158") (name "unconnected-(NET-INT-Pad6)") (class "Default")
      (node (ref "NET") (pin "6") (pinfunction "INT_6") (pintype "passive+no_connect"))
    )
    (net (code "159") (name "unconnected-(NET-NC-Pad9)") (class "Default")
      (node (ref "NET") (pin "9") (pinfunction "NC_9") (pintype "passive+no_connect"))
    )
    (net (code "160") (name "unconnected-(U2-PCTLZ-Pad6)") (class "Default")
      (node (ref "U2") (pin "6") (pinfunction "PCTLZ_6") (pintype "passive+no_connect"))
    )
    (net (code "161") (name "unconnected-(U4-32kHz-Pad1)") (class "Default")
      (node (ref "U4") (pin "1") (pinfunction "32kHz_1") (pintype "passive+no_connect"))
    )
    (net (code "162") (name "unconnected-(U4-INT#{slash}SQW-Pad3)") (class "Default")
      (node (ref "U4") (pin "3") (pinfunction "INT#/SQW_3") (pintype "passive+no_connect"))
    )
    (net (code "163") (name "unconnected-(U4-RST#-Pad4)") (class "Default")
      (node (ref "U4") (pin "4") (pinfunction "RST#_4") (pintype "passive+no_connect"))
    )
    (net (code "164") (name "unconnected-(U8-DU-Pad1)") (class "Default")
      (node (ref "U8") (pin "1") (pinfunction "DU_1") (pintype "passive+no_connect"))
    )
  )
)
